# PedalBoard.net
KiCad netlist of a schematic drawn in Altium Designer
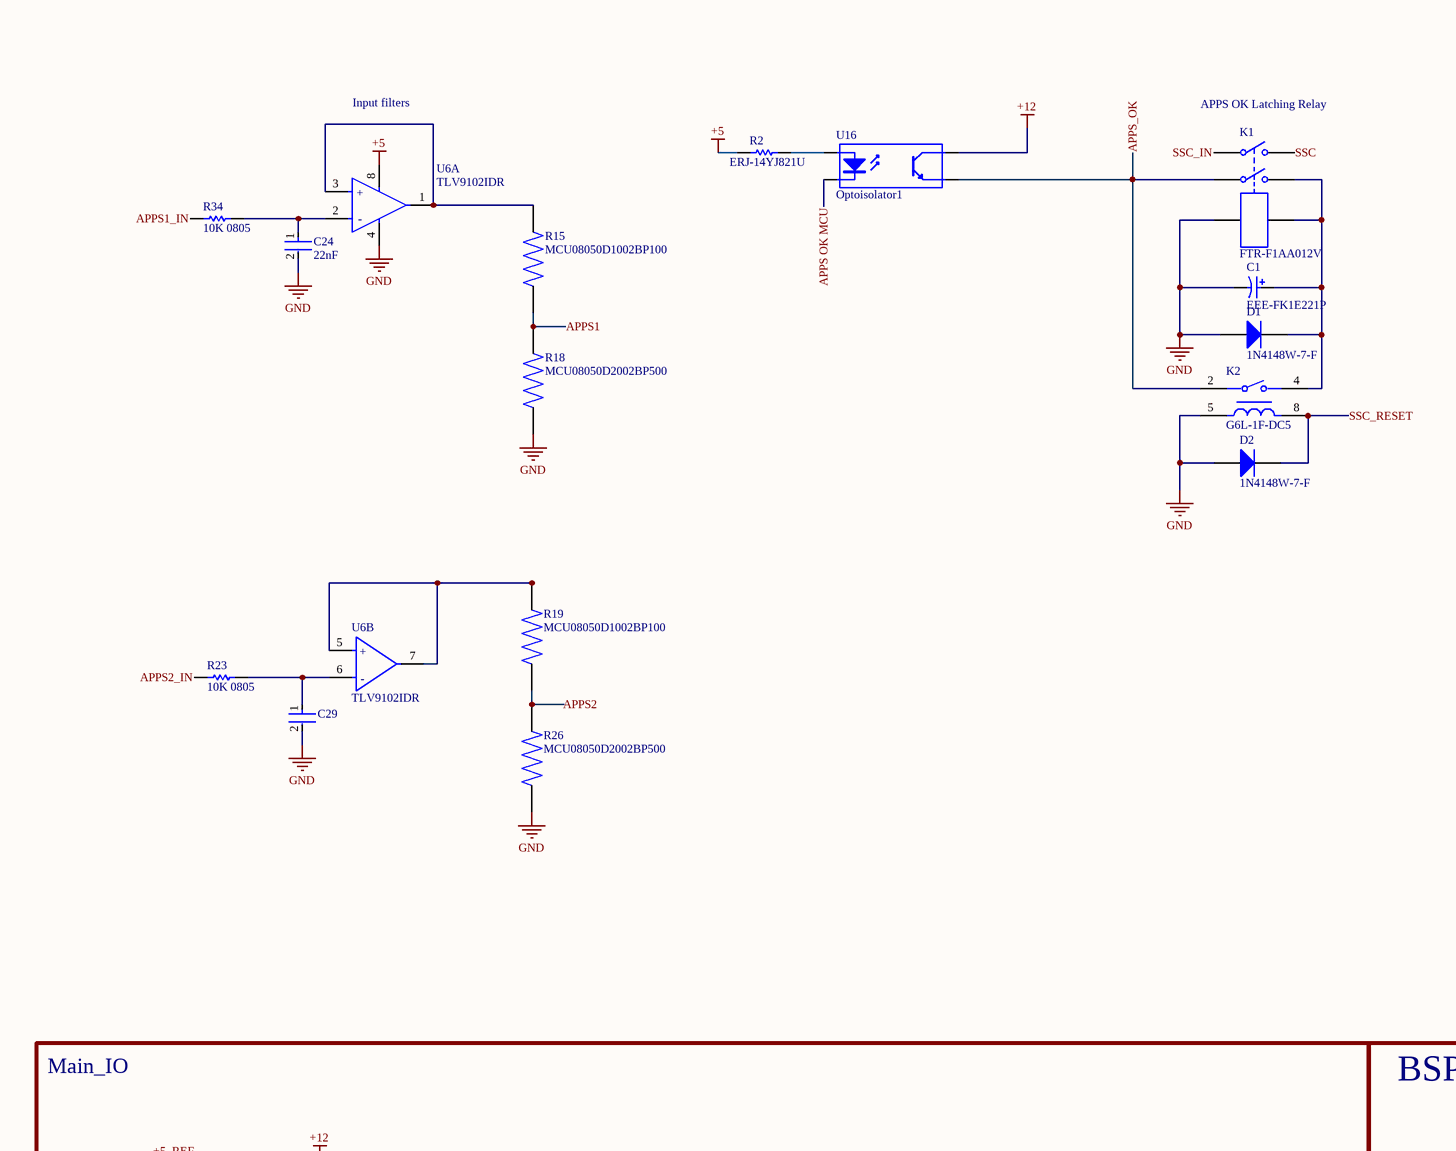
[diagram p0: PedalBoard.SchDoc, top left]
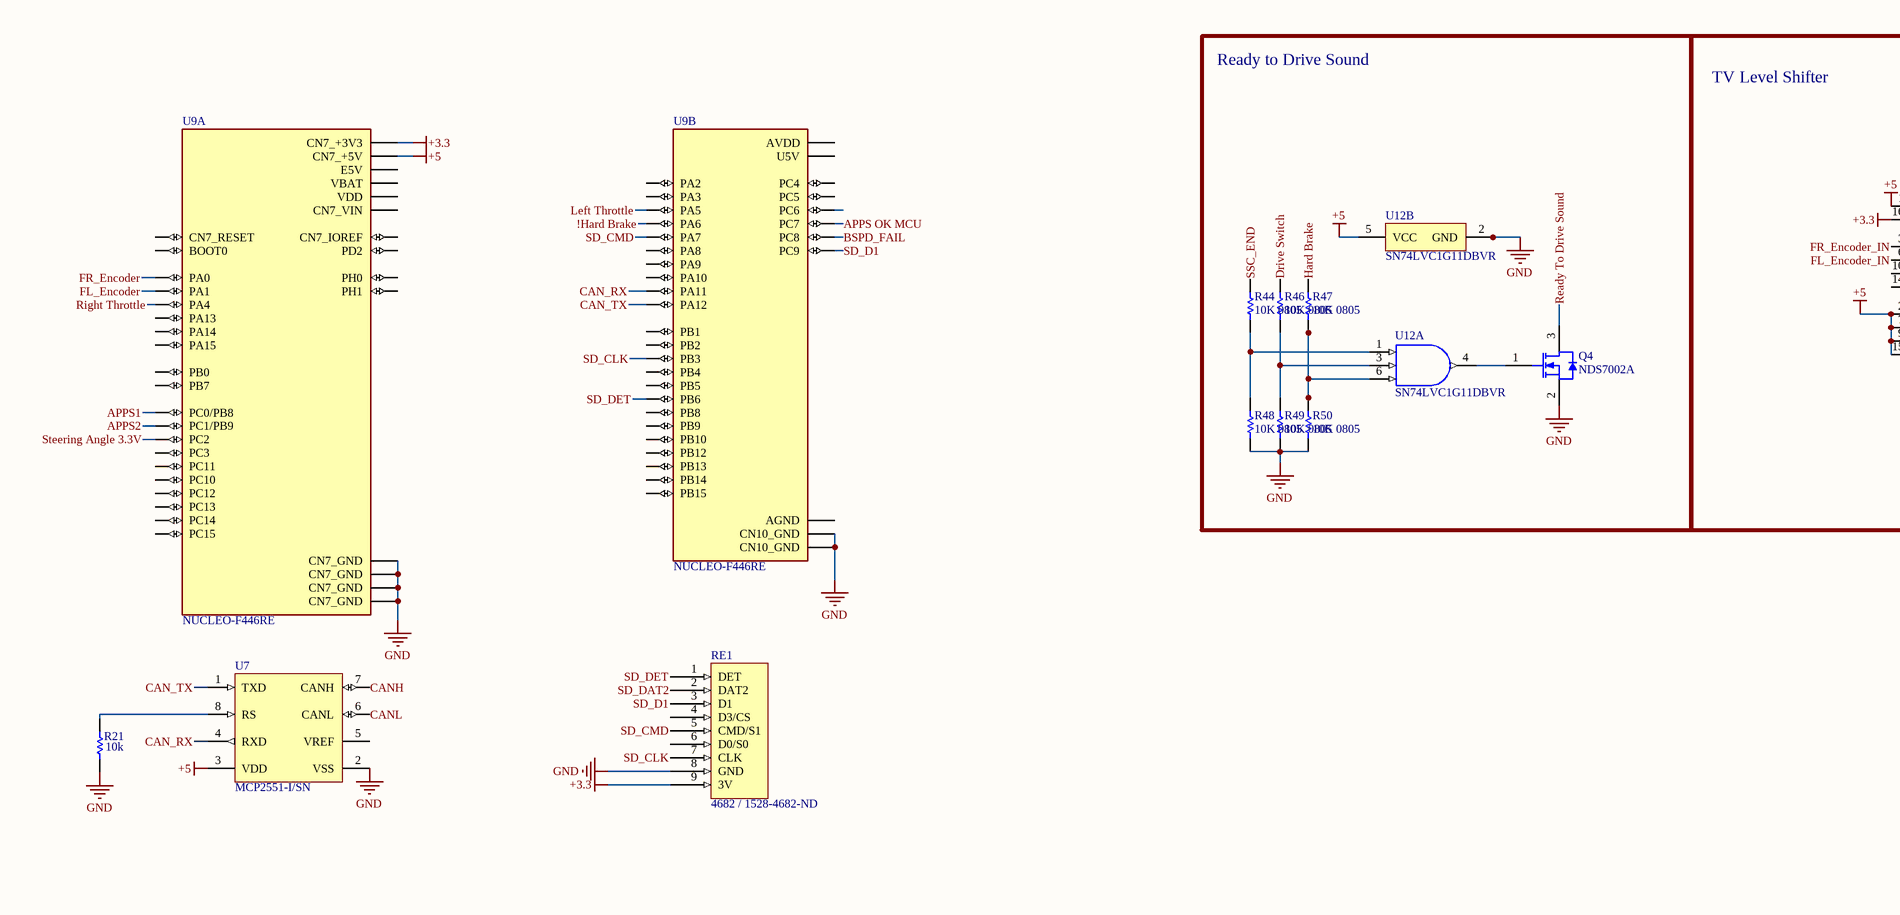
[diagram p1: PedalBoard.SchDoc, top middle]
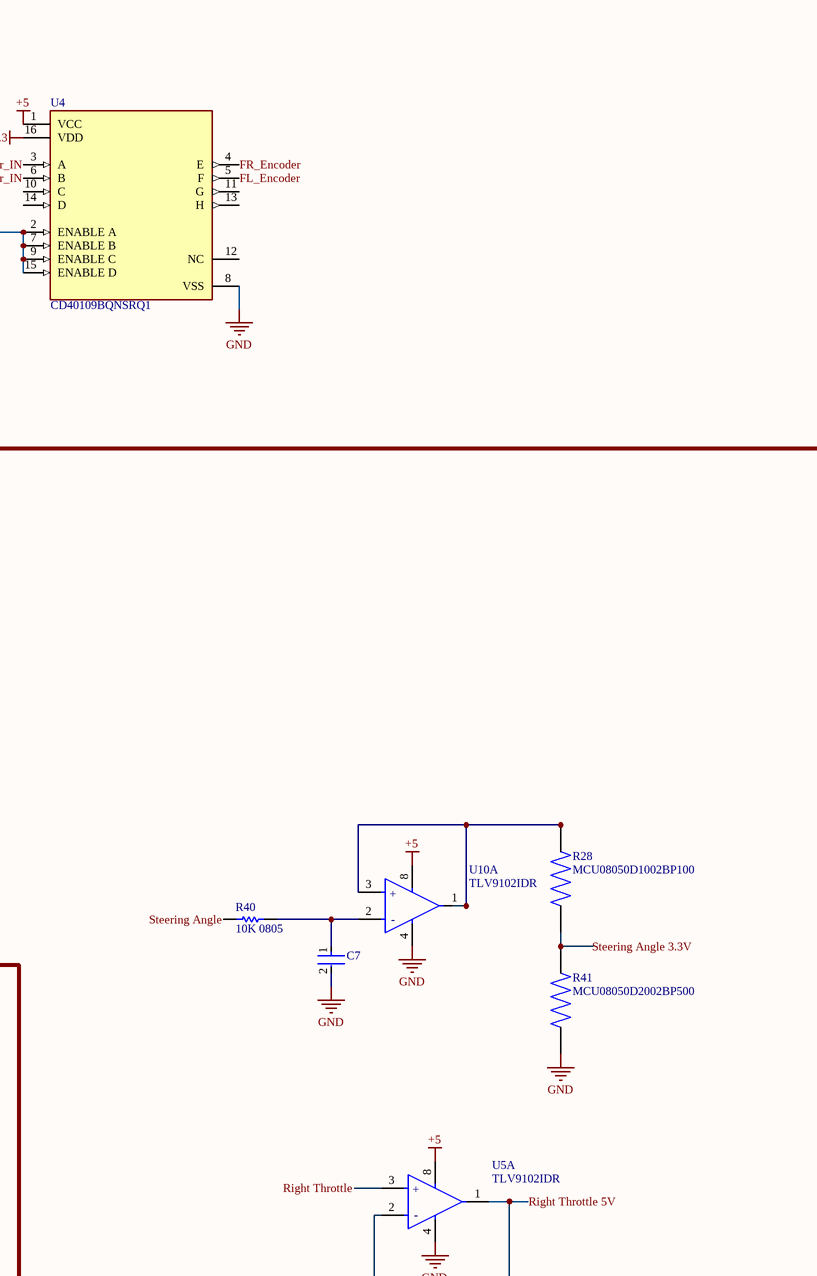
[diagram p2: PedalBoard.SchDoc, top right]
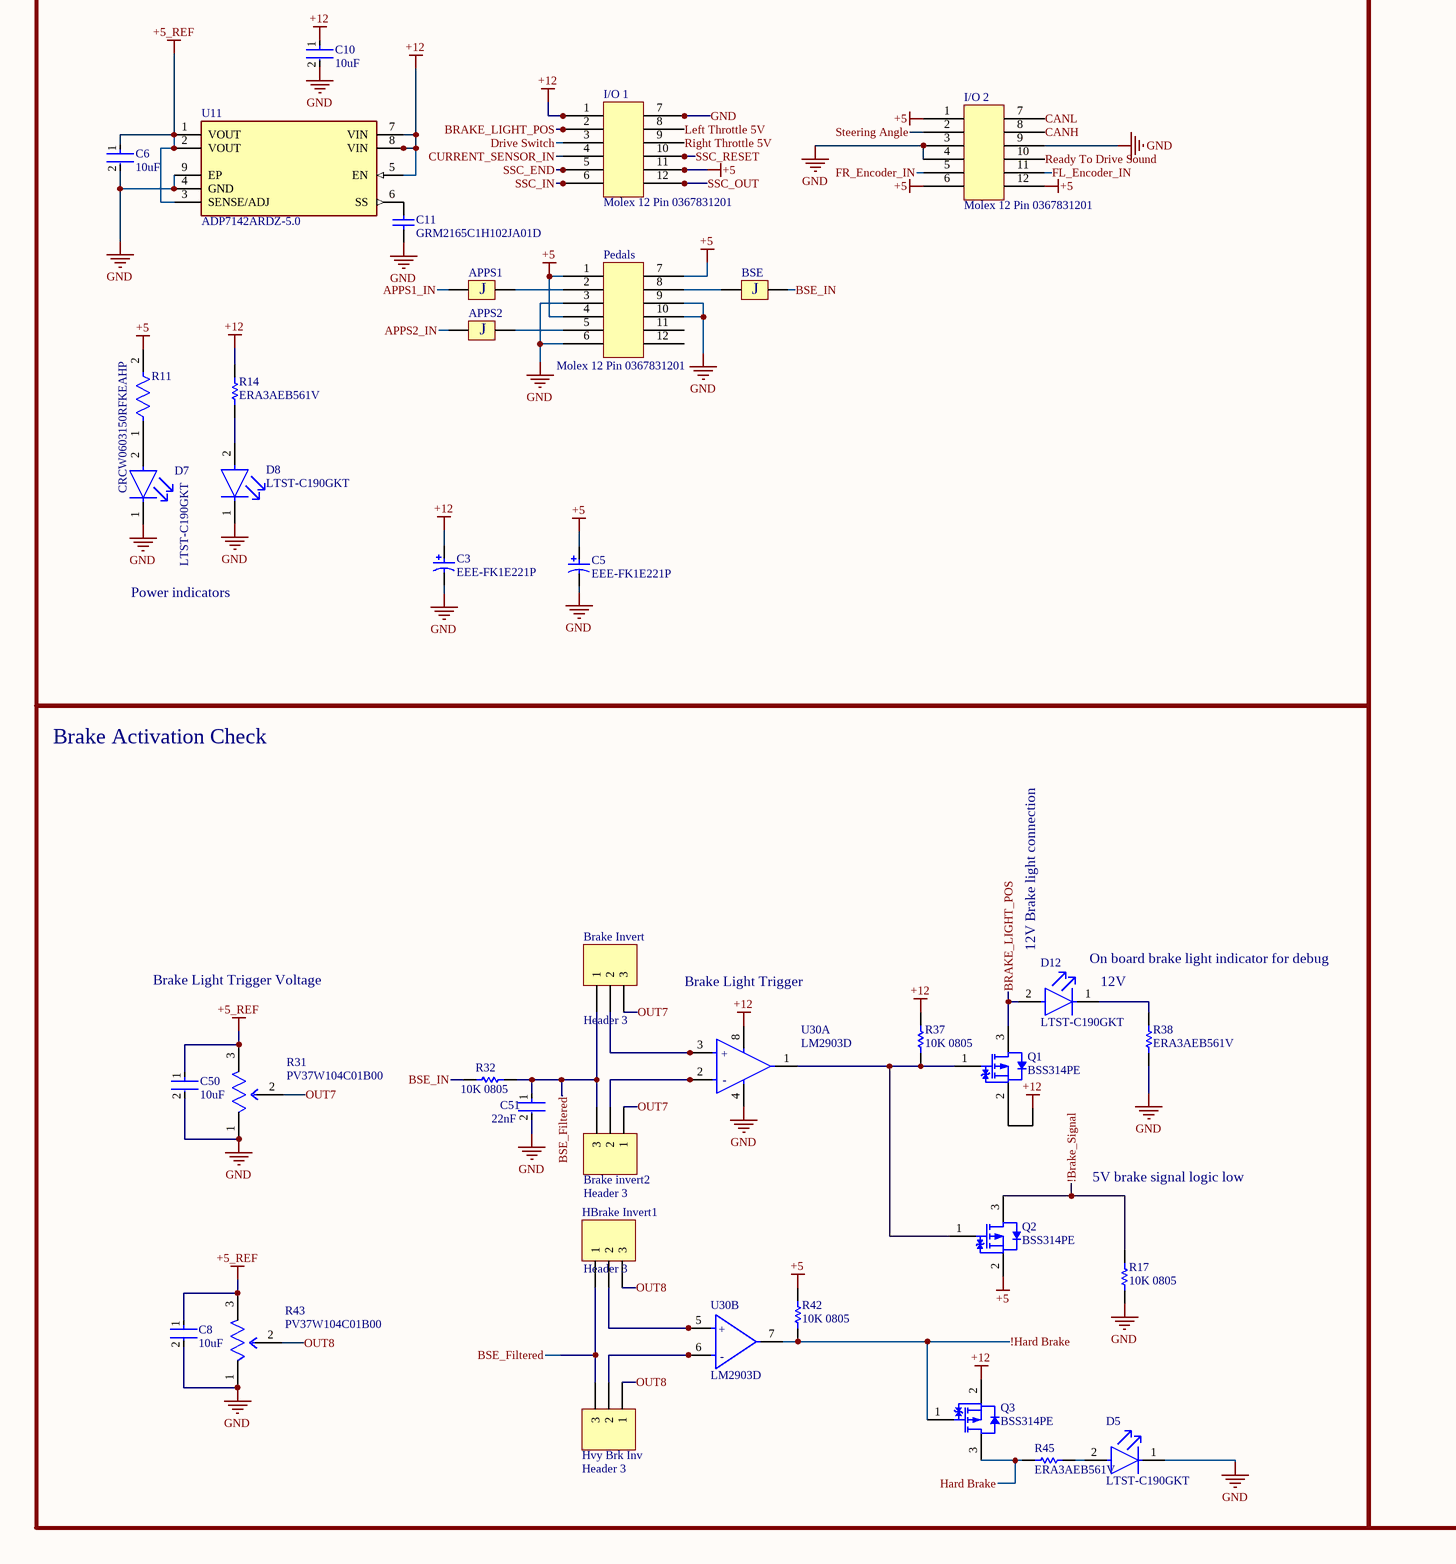
[diagram p3: PedalBoard.SchDoc, bottom left]
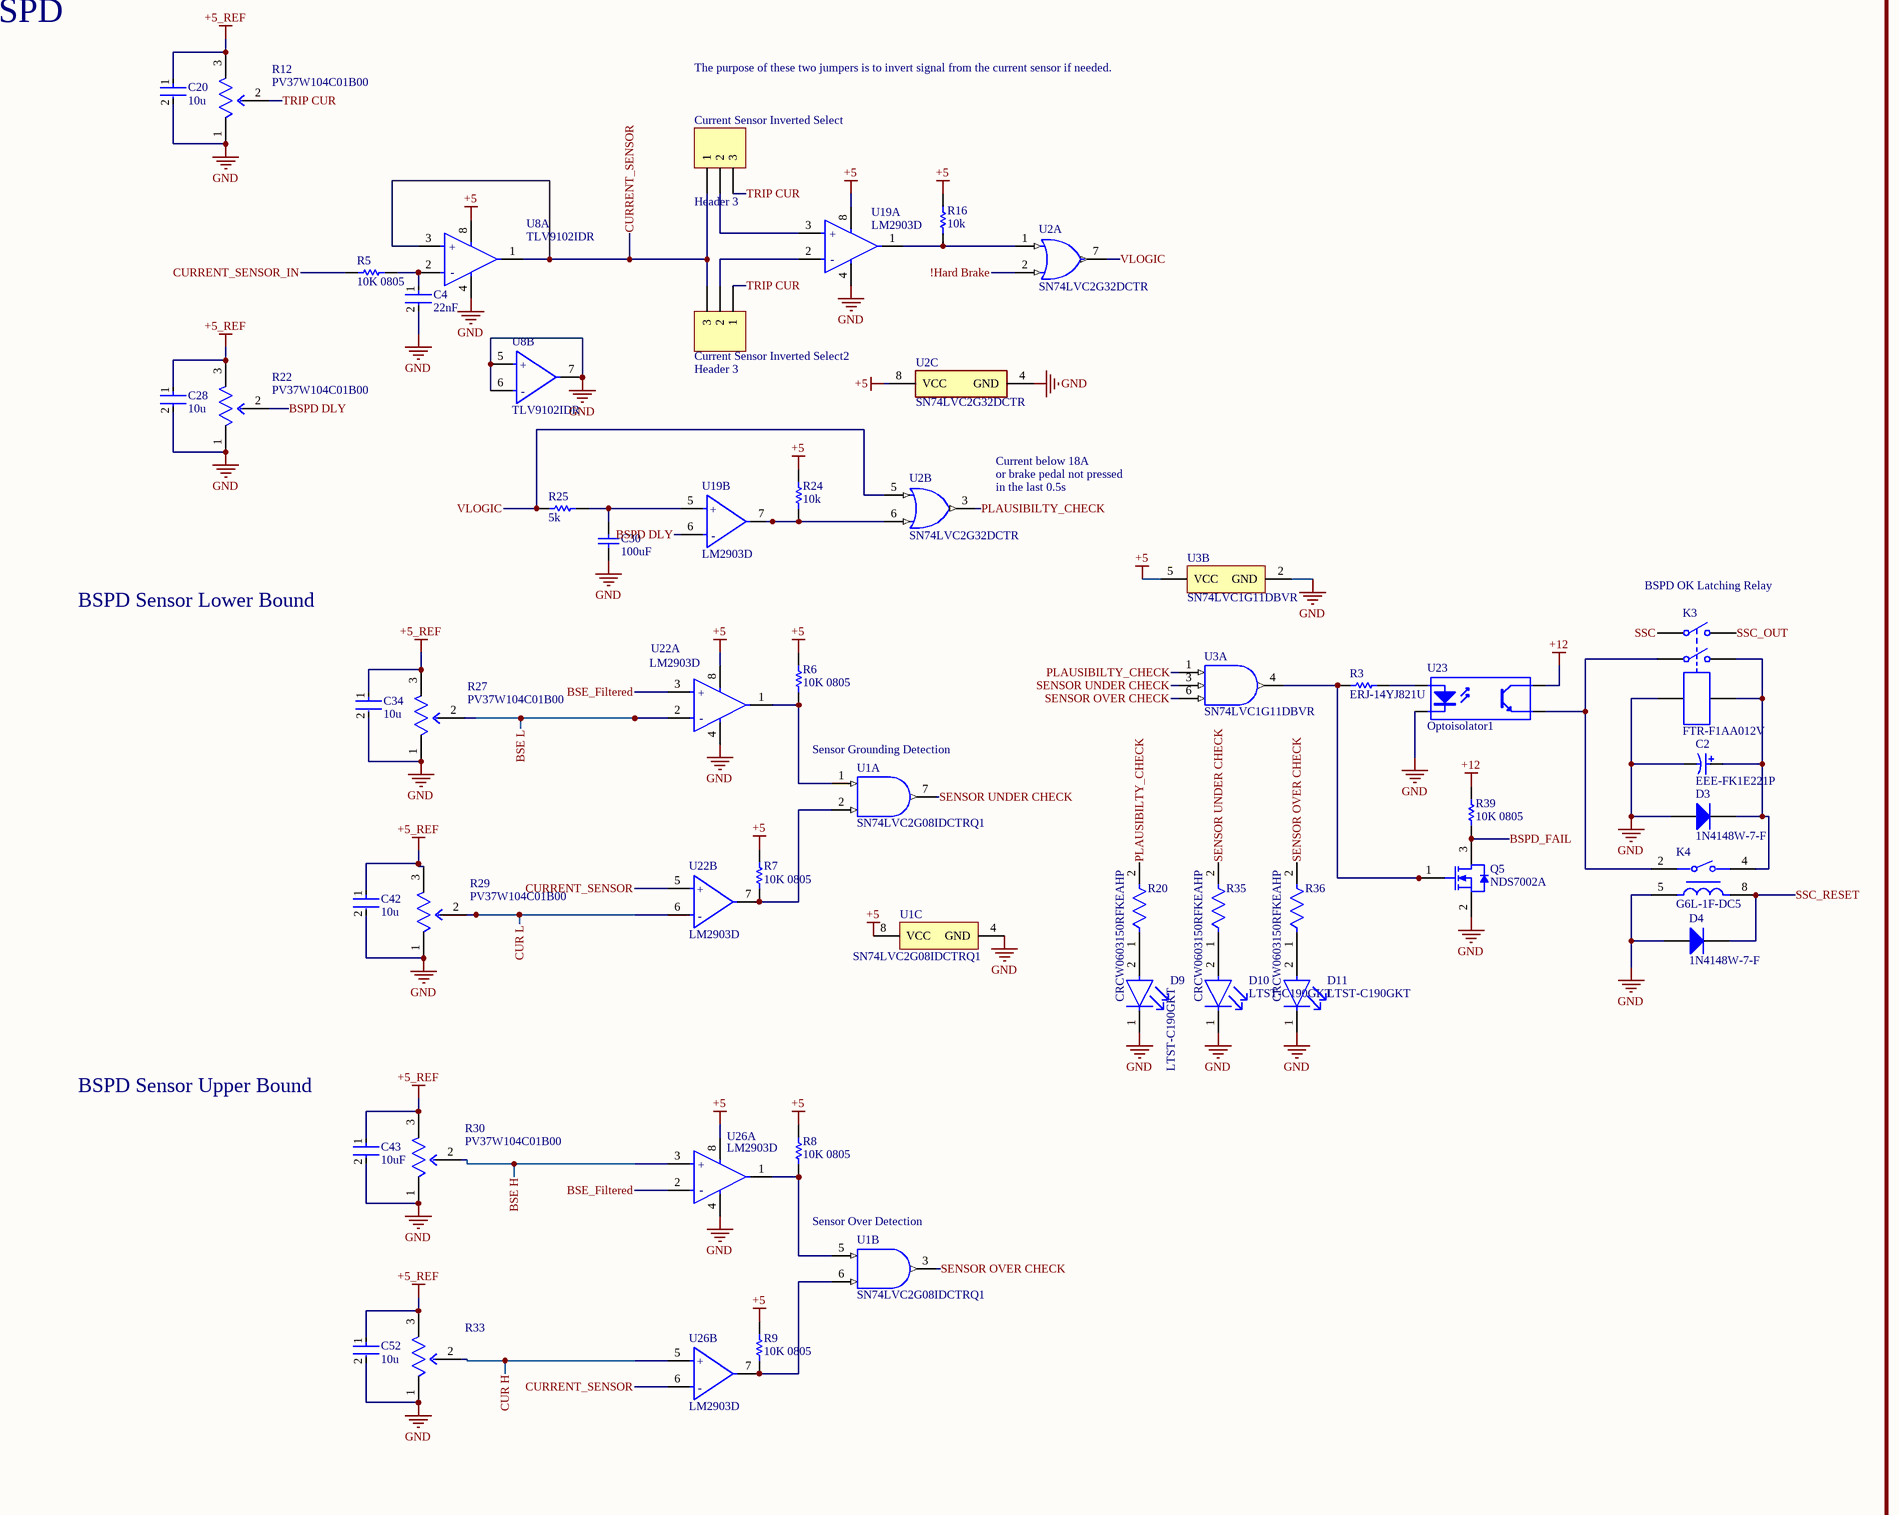
[diagram p4: PedalBoard.SchDoc, bottom middle]
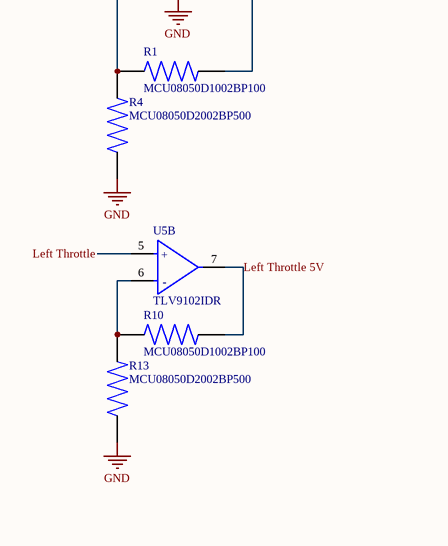
[diagram p5: PedalBoard.SchDoc, bottom right]

(export (version "E")
  (design (tool "Eeschema 10.0.6"))
  (components
    (comp (ref "APPS1")
      (value "Jumper Connector")
      (footprint "Jumper Connector")
      (libsource (lib "PedalControl") (part "Jumper Connector"))
    )
    (comp (ref "APPS2")
      (value "Jumper Connector")
      (footprint "Jumper Connector")
      (libsource (lib "PedalControl") (part "Jumper Connector"))
    )
    (comp (ref "Brake Invert")
      (value "Header 3")
      (footprint "HDR1X3")
      (description "Header, 3-Pin")
      (fields (field (name "PUBLISHER") "Altium Limited"))
      (libsource (lib "Miscellaneous Connectors") (part "Header 3"))
    )
    (comp (ref "Brake invert2")
      (value "Header 3")
      (footprint "HDR1X3")
      (description "Header, 3-Pin")
      (fields (field (name "PUBLISHER") "Altium Limited"))
      (libsource (lib "") (part "Header 3_1"))
    )
    (comp (ref "BSE")
      (value "Jumper Connector")
      (footprint "Jumper Connector")
      (libsource (lib "PedalControl") (part "Jumper Connector"))
    )
    (comp (ref "C1")
      (value "EEE-FK1E221P")
      (footprint "PNSC-EEE-FK1E221P_N")
      (fields (field (name "MANUFACTURER") "Panasonic"))
      (libsource (lib "Altium Content Vault") (part "CAP-P-2"))
    )
    (comp (ref "C2")
      (value "EEE-FK1E221P")
      (footprint "PNSC-EEE-FK1E221P_N")
      (fields (field (name "MANUFACTURER") "Panasonic"))
      (libsource (lib "Altium Content Vault") (part "CAP-P-2"))
    )
    (comp (ref "C3")
      (value "EEE-FK1E221P")
      (footprint "PNSC-EEE-FK1E221P_N")
      (fields (field (name "MANUFACTURER") "Panasonic"))
      (libsource (lib "Altium Content Vault") (part "CAP-P-2"))
    )
    (comp (ref "C4")
      (value "22nF")
      (footprint "FP-C0805C-DN-MFG")
      (description "CAP CER 0.022UF 50V X7R 0805")
      (fields
        (field (name "MANUFACTURER") "KEMET")
        (field (name "MANUFACTURER PART NUMBER") "C0805C223K5RACTU")
      )
      (libsource (lib "Altium Content Vault") (part "b4654b650e69147ec39a6b967a45e02"))
    )
    (comp (ref "C5")
      (value "EEE-FK1E221P")
      (footprint "PNSC-EEE-FK1E221P_N")
      (fields (field (name "MANUFACTURER") "Panasonic"))
      (libsource (lib "Altium Content Vault") (part "CAP-P-2"))
    )
    (comp (ref "C6")
      (value "10uF")
      (footprint "FP-C0603C106M9PACTU-MFG")
      (description "CAP CER 10UF 6.3V X5R 0603")
      (fields
        (field (name "MANUFACTURER PART NUMBER") "C0603C106M9PACTU")
        (field (name "MANUFACTURER") "Kemet")
      )
      (libsource (lib "Altium Content Vault") (part "b4654b650e69147ec39a6b967a45e02"))
    )
    (comp (ref "C7")
      (value "C0805C223K5RACTU")
      (footprint "FP-C0805C-DN-MFG")
      (description "CAP CER 0.022UF 50V X7R 0805")
      (fields
        (field (name "MANUFACTURER") "KEMET")
        (field (name "OCTOPART") "https://octopart.com/c0805c223k5ractu-kemet-145968")
      )
      (libsource (lib "Altium Content Vault") (part "b4654b650e69147ec39a6b967a45e02"))
    )
    (comp (ref "C8")
      (value "10uF")
      (footprint "FP-C0603C106M9PACTU-MFG")
      (description "CAP CER 10UF 6.3V X5R 0603")
      (fields
        (field (name "MANUFACTURER PART NUMBER") "C0603C106M9PACTU")
        (field (name "MANUFACTURER") "Kemet")
      )
      (libsource (lib "Altium Content Vault") (part "b4654b650e69147ec39a6b967a45e02"))
    )
    (comp (ref "C10")
      (value "10uF")
      (footprint "FP-C0603C106M9PACTU-MFG")
      (description "CAP CER 10UF 6.3V X5R 0603")
      (fields
        (field (name "MANUFACTURER PART NUMBER") "C0603C106M9PACTU")
        (field (name "MANUFACTURER") "Kemet")
      )
      (libsource (lib "Altium Content Vault") (part "b4654b650e69147ec39a6b967a45e02"))
    )
    (comp (ref "C11")
      (value "GRM2165C1H102JA01D")
      (footprint "CAPC2013X70X45NL10T25")
      (fields (field (name "MANUFACTURER") "Murata"))
      (libsource (lib "Altium Content Vault") (part "CAP"))
    )
    (comp (ref "C20")
      (value "10u")
      (footprint "FP-C0603C106M9PACTU-MFG")
      (description "CAP CER 10UF 6.3V X5R 0603")
      (fields
        (field (name "MANUFACTURER PART NUMBER") "C0603C106M9PACTU")
        (field (name "MANUFACTURER") "Kemet")
      )
      (libsource (lib "Altium Content Vault") (part "b4654b650e69147ec39a6b967a45e02"))
    )
    (comp (ref "C24")
      (value "22nF")
      (footprint "FP-C0805C-DN-MFG")
      (description "CAP CER 0.022UF 50V X7R 0805")
      (fields
        (field (name "MANUFACTURER") "KEMET")
        (field (name "MANUFACTURER PART NUMBER") "C0805C223K5RACTU")
      )
      (libsource (lib "Altium Content Vault") (part "b4654b650e69147ec39a6b967a45e02"))
    )
    (comp (ref "C28")
      (value "10u")
      (footprint "FP-C0603C106M9PACTU-MFG")
      (description "CAP CER 10UF 6.3V X5R 0603")
      (fields
        (field (name "MANUFACTURER PART NUMBER") "C0603C106M9PACTU")
        (field (name "MANUFACTURER") "Kemet")
      )
      (libsource (lib "Altium Content Vault") (part "b4654b650e69147ec39a6b967a45e02"))
    )
    (comp (ref "C29")
      (value "C0805C223K5RACTU")
      (footprint "FP-C0805C-DN-MFG")
      (description "CAP CER 0.022UF 50V X7R 0805")
      (fields
        (field (name "MANUFACTURER") "KEMET")
        (field (name "OCTOPART") "https://octopart.com/c0805c223k5ractu-kemet-145968")
      )
      (libsource (lib "Altium Content Vault") (part "b4654b650e69147ec39a6b967a45e02"))
    )
    (comp (ref "C30")
      (value "100uF")
      (footprint "CAPC1608X90X35LL15T15")
      (fields (field (name "MANUFACTURER") "Kemet") (field (name "PART NUMBER") "C0603C105K3PAC7867"))
      (libsource (lib "Altium Content Vault") (part "CAP"))
    )
    (comp (ref "C34")
      (value "10u")
      (footprint "FP-C0603C106M9PACTU-MFG")
      (description "CAP CER 10UF 6.3V X5R 0603")
      (fields
        (field (name "MANUFACTURER PART NUMBER") "C0603C106M9PACTU")
        (field (name "MANUFACTURER") "Kemet")
      )
      (libsource (lib "Altium Content Vault") (part "b4654b650e69147ec39a6b967a45e02"))
    )
    (comp (ref "C42")
      (value "10u")
      (footprint "FP-C0603C106M9PACTU-MFG")
      (description "CAP CER 10UF 6.3V X5R 0603")
      (fields
        (field (name "MANUFACTURER PART NUMBER") "C0603C106M9PACTU")
        (field (name "MANUFACTURER") "Kemet")
      )
      (libsource (lib "Altium Content Vault") (part "b4654b650e69147ec39a6b967a45e02"))
    )
    (comp (ref "C43")
      (value "10uF")
      (footprint "FP-C0603C106M9PACTU-MFG")
      (description "CAP CER 10UF 6.3V X5R 0603")
      (fields
        (field (name "MANUFACTURER PART NUMBER") "C0603C106M9PACTU")
        (field (name "MANUFACTURER") "Kemet")
      )
      (libsource (lib "Altium Content Vault") (part "b4654b650e69147ec39a6b967a45e02"))
    )
    (comp (ref "C50")
      (value "10uF")
      (footprint "FP-C0603C106M9PACTU-MFG")
      (description "CAP CER 10UF 6.3V X5R 0603")
      (fields
        (field (name "MANUFACTURER PART NUMBER") "C0603C106M9PACTU")
        (field (name "MANUFACTURER") "Kemet")
      )
      (libsource (lib "Altium Content Vault") (part "b4654b650e69147ec39a6b967a45e02"))
    )
    (comp (ref "C51")
      (value "22nF")
      (footprint "FP-C0805C-DN-MFG")
      (description "CAP CER 0.022UF 50V X7R 0805")
      (fields
        (field (name "MANUFACTURER") "KEMET")
        (field (name "MANUFACTURER PART NUMBER") "C0805C223K5RACTU")
      )
      (libsource (lib "Altium Content Vault") (part "b4654b650e69147ec39a6b967a45e02"))
    )
    (comp (ref "C52")
      (value "10u")
      (footprint "FP-C0603C106M9PACTU-MFG")
      (description "CAP CER 10UF 6.3V X5R 0603")
      (fields
        (field (name "MANUFACTURER PART NUMBER") "C0603C106M9PACTU")
        (field (name "MANUFACTURER") "Kemet")
      )
      (libsource (lib "Altium Content Vault") (part "b4654b650e69147ec39a6b967a45e02"))
    )
    (comp (ref "Current Sensor Inverted Select")
      (value "Header 3")
      (footprint "HDR1X3")
      (description "Header, 3-Pin")
      (fields (field (name "PUBLISHER") "Altium Limited"))
      (libsource (lib "Miscellaneous Connectors") (part "Header 3"))
    )
    (comp (ref "Current Sensor Inverted Select2")
      (value "Header 3")
      (footprint "HDR1X3")
      (description "Header, 3-Pin")
      (fields (field (name "PUBLISHER") "Altium Limited"))
      (libsource (lib "") (part "Header 3_1"))
    )
    (comp (ref "D1")
      (value "1N4148W-7-F")
      (footprint "DIOD-SOD123-2_V")
      (description "Fast Switching Diode, 100 V, 0.15 A, -65 to 150 degC, 2-Pin?SOD123, RoHS, Tape and Reel")
      (fields (field (name "MANUFACTURER") "DiodesIncorporated"))
      (libsource (lib "Altium Content Vault") (part "D-AK-2"))
    )
    (comp (ref "D2")
      (value "1N4148W-7-F")
      (footprint "DIOD-SOD123-2_V")
      (description "Fast Switching Diode, 100 V, 0.15 A, -65 to 150 degC, 2-Pin?SOD123, RoHS, Tape and Reel")
      (fields (field (name "MANUFACTURER") "DiodesIncorporated"))
      (libsource (lib "Altium Content Vault") (part "D-AK-2"))
    )
    (comp (ref "D3")
      (value "1N4148W-7-F")
      (footprint "DIOD-SOD123-2_V")
      (description "Fast Switching Diode, 100 V, 0.15 A, -65 to 150 degC, 2-Pin?SOD123, RoHS, Tape and Reel")
      (fields (field (name "MANUFACTURER") "DiodesIncorporated"))
      (libsource (lib "Altium Content Vault") (part "D-AK-2"))
    )
    (comp (ref "D4")
      (value "1N4148W-7-F")
      (footprint "DIOD-SOD123-2_V")
      (description "Fast Switching Diode, 100 V, 0.15 A, -65 to 150 degC, 2-Pin?SOD123, RoHS, Tape and Reel")
      (fields (field (name "MANUFACTURER") "DiodesIncorporated"))
      (libsource (lib "Altium Content Vault") (part "D-AK-2"))
    )
    (comp (ref "D5")
      (value "LTST-C190GKT")
      (footprint "FP-LTST-C190GKT-MFG")
      (description "LED GREEN CLEAR CHIP SMD")
      (fields (field (name "VOLTAGE") "2V"))
      (libsource (lib "Altium Content Vault") (part "8706943c75ba83719d021d2fdc84c58"))
    )
    (comp (ref "D7")
      (value "LTST-C190GKT")
      (footprint "FP-LTST-C190GKT-MFG")
      (description "LED GREEN CLEAR CHIP SMD")
      (fields (field (name "VOLTAGE") "2V"))
      (libsource (lib "Altium Content Vault") (part "8706943c75ba83719d021d2fdc84c58"))
    )
    (comp (ref "D8")
      (value "LTST-C190GKT")
      (footprint "FP-LTST-C190GKT-MFG")
      (description "LED GREEN CLEAR CHIP SMD")
      (fields (field (name "VOLTAGE") "2V"))
      (libsource (lib "Altium Content Vault") (part "8706943c75ba83719d021d2fdc84c58"))
    )
    (comp (ref "D9")
      (value "LTST-C190GKT")
      (footprint "FP-LTST-C190GKT-MFG")
      (description "LED GREEN CLEAR CHIP SMD")
      (fields (field (name "VOLTAGE") "2V"))
      (libsource (lib "Altium Content Vault") (part "8706943c75ba83719d021d2fdc84c58"))
    )
    (comp (ref "D10")
      (value "LTST-C190GKT")
      (footprint "FP-LTST-C190GKT-MFG")
      (description "LED GREEN CLEAR CHIP SMD")
      (fields (field (name "VOLTAGE") "2V"))
      (libsource (lib "Altium Content Vault") (part "8706943c75ba83719d021d2fdc84c58"))
    )
    (comp (ref "D11")
      (value "LTST-C190GKT")
      (footprint "FP-LTST-C190GKT-MFG")
      (description "LED GREEN CLEAR CHIP SMD")
      (fields (field (name "VOLTAGE") "2V"))
      (libsource (lib "Altium Content Vault") (part "8706943c75ba83719d021d2fdc84c58"))
    )
    (comp (ref "D12")
      (value "LTST-C190GKT")
      (footprint "FP-LTST-C190GKT-MFG")
      (description "LED GREEN CLEAR CHIP SMD")
      (fields (field (name "VOLTAGE") "2V"))
      (libsource (lib "Altium Content Vault") (part "8706943c75ba83719d021d2fdc84c58"))
    )
    (comp (ref "HBrake Invert1")
      (value "Header 3")
      (footprint "HDR1X3")
      (description "Header, 3-Pin")
      (fields (field (name "PUBLISHER") "Altium Limited"))
      (libsource (lib "Miscellaneous Connectors") (part "Header 3"))
    )
    (comp (ref "Hvy Brk Inv")
      (value "Header 3")
      (footprint "HDR1X3")
      (description "Header, 3-Pin")
      (fields (field (name "PUBLISHER") "Altium Limited"))
      (libsource (lib "") (part "Header 3_1"))
    )
    (comp (ref "I/O 1")
      (value "Molex 12 Pin 0367831201")
      (footprint "Molex 12 pos 0367831201 - duplicate")
      (libsource (lib "PedalControl") (part "Molex 12 Pin 0367831201"))
    )
    (comp (ref "I/O 2")
      (value "Molex 12 Pin 0367831201")
      (footprint "Molex 12 pos 0367831201 - duplicate")
      (libsource (lib "PedalControl") (part "Molex 12 Pin 0367831201"))
    )
    (comp (ref "K1")
      (value "FTR-F1AA012V")
      (footprint "FTR-F1AA012V")
      (description "Dual-Pole Single-Throw Relay")
      (fields (field (name "PUBLISHER") "Altium Limited"))
      (libsource (lib "Miscellaneous Devices") (part "Relay-DPST"))
    )
    (comp (ref "K2")
      (value "G6L-1F-DC5")
      (footprint "FP-G6L-1F-DC5-MFG")
      (description "RELAY TELECOM SPST 1A 5VDC")
      (fields
        (field (name "MANUFACTURER") "Omron")
        (field (name "OCTOPART") "https://octopart.com/g6l-1f+dc5-omron-18903080")
      )
      (libsource (lib "Altium Content Vault") (part "0b4cad2df39780911da7817dc4dbd4a"))
    )
    (comp (ref "K3")
      (value "FTR-F1AA012V")
      (footprint "FTR-F1AA012V")
      (description "Dual-Pole Single-Throw Relay")
      (fields (field (name "PUBLISHER") "Altium Limited"))
      (libsource (lib "Miscellaneous Devices") (part "Relay-DPST"))
    )
    (comp (ref "K4")
      (value "G6L-1F-DC5")
      (footprint "FP-G6L-1F-DC5-MFG")
      (description "RELAY TELECOM SPST 1A 5VDC")
      (fields
        (field (name "MANUFACTURER") "Omron")
        (field (name "OCTOPART") "https://octopart.com/g6l-1f+dc5-omron-18903080")
      )
      (libsource (lib "Altium Content Vault") (part "0b4cad2df39780911da7817dc4dbd4a"))
    )
    (comp (ref "Pedals")
      (value "Molex 12 Pin 0367831201")
      (footprint "Molex 12 pos 0367831201 - duplicate")
      (libsource (lib "PedalControl") (part "Molex 12 Pin 0367831201"))
    )
    (comp (ref "Q1")
      (value "BSS314PE")
      (footprint "INF-PG-SOT23_N")
      (fields (field (name "MANUFACTURER") "Infineon"))
      (libsource (lib "Altium Content Vault") (part "INF-BSS3XXPE-PG-SOT23-3"))
    )
    (comp (ref "Q2")
      (value "BSS314PE")
      (footprint "INF-PG-SOT23_N")
      (fields (field (name "MANUFACTURER") "Infineon"))
      (libsource (lib "Altium Content Vault") (part "INF-BSS3XXPE-PG-SOT23-3"))
    )
    (comp (ref "Q3")
      (value "BSS314PE")
      (footprint "INF-PG-SOT23_N")
      (fields (field (name "MANUFACTURER") "Infineon"))
      (libsource (lib "Altium Content Vault") (part "INF-BSS3XXPE-PG-SOT23-3"))
    )
    (comp (ref "Q4")
      (value "NDS7002A")
      (footprint "FAIR-SOT23-3_V")
      (fields (field (name "MANUFACTURER") "Fairchild Semiconductor"))
      (libsource (lib "Altium Content Vault") (part "NEMOS-GSD-3"))
    )
    (comp (ref "Q5")
      (value "NDS7002A")
      (footprint "FAIR-SOT23-3_V")
      (fields (field (name "MANUFACTURER") "Fairchild Semiconductor"))
      (libsource (lib "Altium Content Vault") (part "NEMOS-GSD-3"))
    )
    (comp (ref "R1")
      (value "MCU08050D1002BP100")
      (footprint "MCU08050D1002BP100:RESC2012X55N")
      (description "Res Thin Film 0805 10K Ohm 0.1% 0.125W(1/8W) Â±25ppm/C SMD Automotive Medical T/R")
      (fields (field (name "MF") "{'manufacturer': u'Vishay'}"))
      (libsource (lib "*") (part "MCU08050D1002BP100"))
    )
    (comp (ref "R2")
      (value "ERJ-14YJ821U")
      (footprint "RESC3225X70X50LL20T20")
      (description "820")
      (fields (field (name "MANUFACTURER") "Panasonic"))
      (libsource (lib "Altium Content Vault") (part "RES"))
    )
    (comp (ref "R3")
      (value "ERJ-14YJ821U")
      (footprint "RESC3225X70X50LL20T20")
      (description "820")
      (fields (field (name "MANUFACTURER") "Panasonic"))
      (libsource (lib "Altium Content Vault") (part "RES"))
    )
    (comp (ref "R4")
      (value "MCU08050D2002BP500")
      (footprint "MCU08050D2002BP500:RESC2012X55N")
      (description "RES -FILM RESISTORS-THICK FILM CHIP")
      (fields (field (name "MF") "{'manufacturer': u'Vishay'}"))
      (libsource (lib "*") (part "MCU08050D2002BP500"))
    )
    (comp (ref "R5")
      (value "10K 0805")
      (footprint "RESC2013X60X35NL10T20")
      (description "Chip Resistor, 10 KOhm, +/- 1%, 0.125 W, -55 to 155 degC, 0805 (2012 Metric), RoHS, Tape and Reel")
      (fields (field (name "MANUFACTURER") "Yageo"))
      (libsource (lib "Altium Content Vault") (part "RES-2"))
    )
    (comp (ref "R6")
      (value "10K 0805")
      (footprint "RESC2013X60X35NL10T20")
      (description "Chip Resistor, 10 KOhm, +/- 1%, 0.125 W, -55 to 155 degC, 0805 (2012 Metric), RoHS, Tape and Reel")
      (fields (field (name "MANUFACTURER") "Yageo"))
      (libsource (lib "Altium Content Vault") (part "RES-2"))
    )
    (comp (ref "R7")
      (value "10K 0805")
      (footprint "RESC2013X60X35NL10T20")
      (description "Chip Resistor, 10 KOhm, +/- 1%, 0.125 W, -55 to 155 degC, 0805 (2012 Metric), RoHS, Tape and Reel")
      (fields (field (name "MANUFACTURER") "Yageo"))
      (libsource (lib "Altium Content Vault") (part "RES-2"))
    )
    (comp (ref "R8")
      (value "10K 0805")
      (footprint "RESC2013X60X35NL10T20")
      (description "Chip Resistor, 10 KOhm, +/- 1%, 0.125 W, -55 to 155 degC, 0805 (2012 Metric), RoHS, Tape and Reel")
      (fields (field (name "MANUFACTURER") "Yageo"))
      (libsource (lib "Altium Content Vault") (part "RES-2"))
    )
    (comp (ref "R9")
      (value "10K 0805")
      (footprint "RESC2013X60X35NL10T20")
      (description "Chip Resistor, 10 KOhm, +/- 1%, 0.125 W, -55 to 155 degC, 0805 (2012 Metric), RoHS, Tape and Reel")
      (fields (field (name "MANUFACTURER") "Yageo"))
      (libsource (lib "Altium Content Vault") (part "RES-2"))
    )
    (comp (ref "R10")
      (value "MCU08050D1002BP100")
      (footprint "MCU08050D1002BP100:RESC2012X55N")
      (description "Res Thin Film 0805 10K Ohm 0.1% 0.125W(1/8W) Â±25ppm/C SMD Automotive Medical T/R")
      (fields (field (name "MF") "{'manufacturer': u'Vishay'}"))
      (libsource (lib "*") (part "MCU08050D1002BP100"))
    )
    (comp (ref "R11")
      (value "CRCW0603150RFKEAHP")
      (footprint "FP-CRCW0603-HPe3-MFG")
      (description "RES Thick Film, 150Ω, 1%, 0.33W, 100ppm/°C, 0603")
      (fields (field (name "TOLERANCE") "1%"))
      (libsource (lib "Altium Content Vault") (part "1029c3af85768c4190bb7ad29bc67b5"))
    )
    (comp (ref "R12")
      (value "PV37W104C01B00")
      (footprint "FP-PV37W104C01B00-MFG")
      (description "12-Turn Through Hole Trimmer Resistor with Pin Terminations, 10% 1/4W 150ppm/C")
      (fields (field (name "TOLERANCE") "10%"))
      (libsource (lib "Altium Content Vault") (part "08526ac0d5a9b3c124616c1f8dc5852"))
    )
    (comp (ref "R13")
      (value "MCU08050D2002BP500")
      (footprint "MCU08050D2002BP500:RESC2012X55N")
      (description "RES -FILM RESISTORS-THICK FILM CHIP")
      (fields (field (name "MF") "{'manufacturer': u'Vishay'}"))
      (libsource (lib "*") (part "MCU08050D2002BP500"))
    )
    (comp (ref "R14")
      (value "ERA3AEB561V")
      (footprint "RESC1608X55X30LL20T20")
      (fields (field (name "MANUFACTURER") "Panasonic"))
      (libsource (lib "Altium Content Vault") (part "RES"))
    )
    (comp (ref "R15")
      (value "MCU08050D1002BP100")
      (footprint "MCU08050D1002BP100:RESC2012X55N")
      (description "Res Thin Film 0805 10K Ohm 0.1% 0.125W(1/8W) Â±25ppm/C SMD Automotive Medical T/R")
      (fields (field (name "MF") "{'manufacturer': u'Vishay'}"))
      (libsource (lib "*") (part "MCU08050D1002BP100"))
    )
    (comp (ref "R16")
      (value "10k")
      (footprint "RESC1609X55X30LL15T15")
      (description "Chip Resistor, 10 KOhm, +/- 1%, 0.1 W, -55 to 155 degC, 0603 (1608 Metric), RoHS, Tape and Reel")
      (fields (field (name "TOLERANCE") "1%") (field (name "MANUFACTURER") "Panasonic"))
      (libsource (lib "Altium Content Vault") (part "RES-2"))
    )
    (comp (ref "R17")
      (value "10K 0805")
      (footprint "RESC2013X60X35NL10T20")
      (description "Chip Resistor, 10 KOhm, +/- 1%, 0.125 W, -55 to 155 degC, 0805 (2012 Metric), RoHS, Tape and Reel")
      (fields (field (name "MANUFACTURER") "Yageo"))
      (libsource (lib "Altium Content Vault") (part "RES-2"))
    )
    (comp (ref "R18")
      (value "MCU08050D2002BP500")
      (footprint "MCU08050D2002BP500:RESC2012X55N")
      (description "RES -FILM RESISTORS-THICK FILM CHIP")
      (fields (field (name "MF") "{'manufacturer': u'Vishay'}"))
      (libsource (lib "*") (part "MCU08050D2002BP500"))
    )
    (comp (ref "R19")
      (value "MCU08050D1002BP100")
      (footprint "MCU08050D1002BP100:RESC2012X55N")
      (description "Res Thin Film 0805 10K Ohm 0.1% 0.125W(1/8W) Â±25ppm/C SMD Automotive Medical T/R")
      (fields (field (name "MF") "{'manufacturer': u'Vishay'}"))
      (libsource (lib "*") (part "MCU08050D1002BP100"))
    )
    (comp (ref "R20")
      (value "CRCW0603150RFKEAHP")
      (footprint "FP-CRCW0603-HPe3-MFG")
      (description "RES Thick Film, 150Ω, 1%, 0.33W, 100ppm/°C, 0603")
      (fields (field (name "TOLERANCE") "1%"))
      (libsource (lib "Altium Content Vault") (part "1029c3af85768c4190bb7ad29bc67b5"))
    )
    (comp (ref "R21")
      (value "10k")
      (footprint "RESC1609X55X30LL15T15")
      (description "Chip Resistor, 10 KOhm, +/- 1%, 0.1 W, -55 to 155 degC, 0603 (1608 Metric), RoHS, Tape and Reel")
      (fields (field (name "TOLERANCE") "1%") (field (name "MANUFACTURER") "Panasonic"))
      (libsource (lib "Altium Content Vault") (part "RES-2"))
    )
    (comp (ref "R22")
      (value "PV37W104C01B00")
      (footprint "FP-PV37W104C01B00-MFG")
      (description "12-Turn Through Hole Trimmer Resistor with Pin Terminations, 10% 1/4W 150ppm/C")
      (fields (field (name "TOLERANCE") "10%"))
      (libsource (lib "Altium Content Vault") (part "08526ac0d5a9b3c124616c1f8dc5852"))
    )
    (comp (ref "R23")
      (value "10K 0805")
      (footprint "RESC2013X60X35NL10T20")
      (description "Chip Resistor, 10 KOhm, +/- 1%, 0.125 W, -55 to 155 degC, 0805 (2012 Metric), RoHS, Tape and Reel")
      (fields (field (name "MANUFACTURER") "Yageo"))
      (libsource (lib "Altium Content Vault") (part "RES-2"))
    )
    (comp (ref "R24")
      (value "10k")
      (footprint "RESC1609X55X30LL15T15")
      (description "Chip Resistor, 10 KOhm, +/- 1%, 0.1 W, -55 to 155 degC, 0603 (1608 Metric), RoHS, Tape and Reel")
      (fields (field (name "TOLERANCE") "1%") (field (name "MANUFACTURER") "Panasonic"))
      (libsource (lib "Altium Content Vault") (part "RES-2"))
    )
    (comp (ref "R25")
      (value "5k")
      (footprint "RESC1609X55X30LL15T15")
      (description "Chip Resistor, 10 KOhm, +/- 1%, 0.1 W, -55 to 155 degC, 0603 (1608 Metric), RoHS, Tape and Reel")
      (fields (field (name "TOLERANCE") "1%") (field (name "MANUFACTURER") "Panasonic"))
      (libsource (lib "Altium Content Vault") (part "RES-2"))
    )
    (comp (ref "R26")
      (value "MCU08050D2002BP500")
      (footprint "MCU08050D2002BP500:RESC2012X55N")
      (description "RES -FILM RESISTORS-THICK FILM CHIP")
      (fields (field (name "MF") "{'manufacturer': u'Vishay'}"))
      (libsource (lib "*") (part "MCU08050D2002BP500"))
    )
    (comp (ref "R27")
      (value "PV37W104C01B00")
      (footprint "FP-PV37W104C01B00-MFG")
      (description "12-Turn Through Hole Trimmer Resistor with Pin Terminations, 10% 1/4W 150ppm/C")
      (fields (field (name "TOLERANCE") "10%"))
      (libsource (lib "Altium Content Vault") (part "08526ac0d5a9b3c124616c1f8dc5852"))
    )
    (comp (ref "R28")
      (value "MCU08050D1002BP100")
      (footprint "MCU08050D1002BP100:RESC2012X55N")
      (description "Res Thin Film 0805 10K Ohm 0.1% 0.125W(1/8W) Â±25ppm/C SMD Automotive Medical T/R")
      (fields (field (name "MF") "{'manufacturer': u'Vishay'}"))
      (libsource (lib "*") (part "MCU08050D1002BP100"))
    )
    (comp (ref "R29")
      (value "PV37W104C01B00")
      (footprint "FP-PV37W104C01B00-MFG")
      (description "12-Turn Through Hole Trimmer Resistor with Pin Terminations, 10% 1/4W 150ppm/C")
      (fields (field (name "TOLERANCE") "10%"))
      (libsource (lib "Altium Content Vault") (part "08526ac0d5a9b3c124616c1f8dc5852"))
    )
    (comp (ref "R30")
      (value "PV37W104C01B00")
      (footprint "FP-PV37W104C01B00-MFG")
      (description "12-Turn Through Hole Trimmer Resistor with Pin Terminations, 10% 1/4W 150ppm/C")
      (fields (field (name "TOLERANCE") "10%"))
      (libsource (lib "Altium Content Vault") (part "08526ac0d5a9b3c124616c1f8dc5852"))
    )
    (comp (ref "R31")
      (value "PV37W104C01B00")
      (footprint "FP-PV37W104C01B00-MFG")
      (description "12-Turn Through Hole Trimmer Resistor with Pin Terminations, 10% 1/4W 150ppm/C")
      (fields (field (name "TOLERANCE") "10%"))
      (libsource (lib "Altium Content Vault") (part "08526ac0d5a9b3c124616c1f8dc5852"))
    )
    (comp (ref "R32")
      (value "10K 0805")
      (footprint "RESC2013X60X35NL10T20")
      (description "Chip Resistor, 10 KOhm, +/- 1%, 0.125 W, -55 to 155 degC, 0805 (2012 Metric), RoHS, Tape and Reel")
      (fields (field (name "MANUFACTURER") "Yageo"))
      (libsource (lib "Altium Content Vault") (part "RES-2"))
    )
    (comp (ref "R33")
      (value "PV37W104C01B00")
      (footprint "FP-PV37W104C01B00-MFG")
      (description "12-Turn Through Hole Trimmer Resistor with Pin Terminations, 10% 1/4W 150ppm/C")
      (fields (field (name "TOLERANCE") "10%"))
      (libsource (lib "Altium Content Vault") (part "08526ac0d5a9b3c124616c1f8dc5852"))
    )
    (comp (ref "R34")
      (value "10K 0805")
      (footprint "RESC2013X60X35NL10T20")
      (description "Chip Resistor, 10 KOhm, +/- 1%, 0.125 W, -55 to 155 degC, 0805 (2012 Metric), RoHS, Tape and Reel")
      (fields (field (name "MANUFACTURER") "Yageo"))
      (libsource (lib "Altium Content Vault") (part "RES-2"))
    )
    (comp (ref "R35")
      (value "CRCW0603150RFKEAHP")
      (footprint "FP-CRCW0603-HPe3-MFG")
      (description "RES Thick Film, 150Ω, 1%, 0.33W, 100ppm/°C, 0603")
      (fields (field (name "TOLERANCE") "1%"))
      (libsource (lib "Altium Content Vault") (part "1029c3af85768c4190bb7ad29bc67b5"))
    )
    (comp (ref "R36")
      (value "CRCW0603150RFKEAHP")
      (footprint "FP-CRCW0603-HPe3-MFG")
      (description "RES Thick Film, 150Ω, 1%, 0.33W, 100ppm/°C, 0603")
      (fields (field (name "TOLERANCE") "1%"))
      (libsource (lib "Altium Content Vault") (part "1029c3af85768c4190bb7ad29bc67b5"))
    )
    (comp (ref "R37")
      (value "10K 0805")
      (footprint "RESC2013X60X35NL10T20")
      (description "Chip Resistor, 10 KOhm, +/- 1%, 0.125 W, -55 to 155 degC, 0805 (2012 Metric), RoHS, Tape and Reel")
      (fields (field (name "MANUFACTURER") "Yageo"))
      (libsource (lib "Altium Content Vault") (part "RES-2"))
    )
    (comp (ref "R38")
      (value "ERA3AEB561V")
      (footprint "RESC1608X55X30LL20T20")
      (fields (field (name "MANUFACTURER") "Panasonic"))
      (libsource (lib "Altium Content Vault") (part "RES"))
    )
    (comp (ref "R39")
      (value "10K 0805")
      (footprint "RESC2013X60X35NL10T20")
      (description "Chip Resistor, 10 KOhm, +/- 1%, 0.125 W, -55 to 155 degC, 0805 (2012 Metric), RoHS, Tape and Reel")
      (fields (field (name "MANUFACTURER") "Yageo"))
      (libsource (lib "Altium Content Vault") (part "RES-2"))
    )
    (comp (ref "R40")
      (value "10K 0805")
      (footprint "RESC2013X60X35NL10T20")
      (description "Chip Resistor, 10 KOhm, +/- 1%, 0.125 W, -55 to 155 degC, 0805 (2012 Metric), RoHS, Tape and Reel")
      (fields (field (name "MANUFACTURER") "Yageo"))
      (libsource (lib "Altium Content Vault") (part "RES-2"))
    )
    (comp (ref "R41")
      (value "MCU08050D2002BP500")
      (footprint "MCU08050D2002BP500:RESC2012X55N")
      (description "RES -FILM RESISTORS-THICK FILM CHIP")
      (fields (field (name "MF") "{'manufacturer': u'Vishay'}"))
      (libsource (lib "*") (part "MCU08050D2002BP500"))
    )
    (comp (ref "R42")
      (value "10K 0805")
      (footprint "RESC2013X60X35NL10T20")
      (description "Chip Resistor, 10 KOhm, +/- 1%, 0.125 W, -55 to 155 degC, 0805 (2012 Metric), RoHS, Tape and Reel")
      (fields (field (name "MANUFACTURER") "Yageo"))
      (libsource (lib "Altium Content Vault") (part "RES-2"))
    )
    (comp (ref "R43")
      (value "PV37W104C01B00")
      (footprint "FP-PV37W104C01B00-MFG")
      (description "12-Turn Through Hole Trimmer Resistor with Pin Terminations, 10% 1/4W 150ppm/C")
      (fields (field (name "TOLERANCE") "10%"))
      (libsource (lib "Altium Content Vault") (part "08526ac0d5a9b3c124616c1f8dc5852"))
    )
    (comp (ref "R44")
      (value "10K 0805")
      (footprint "RESC2013X60X35NL10T20")
      (description "Chip Resistor, 10 KOhm, +/- 1%, 0.125 W, -55 to 155 degC, 0805 (2012 Metric), RoHS, Tape and Reel")
      (fields (field (name "MANUFACTURER") "Yageo"))
      (libsource (lib "Altium Content Vault") (part "RES-2"))
    )
    (comp (ref "R45")
      (value "ERA3AEB561V")
      (footprint "RESC1608X55X30LL20T20")
      (fields (field (name "MANUFACTURER") "Panasonic"))
      (libsource (lib "Altium Content Vault") (part "RES"))
    )
    (comp (ref "R46")
      (value "10K 0805")
      (footprint "RESC2013X60X35NL10T20")
      (description "Chip Resistor, 10 KOhm, +/- 1%, 0.125 W, -55 to 155 degC, 0805 (2012 Metric), RoHS, Tape and Reel")
      (fields (field (name "MANUFACTURER") "Yageo"))
      (libsource (lib "Altium Content Vault") (part "RES-2"))
    )
    (comp (ref "R47")
      (value "10K 0805")
      (footprint "RESC2013X60X35NL10T20")
      (description "Chip Resistor, 10 KOhm, +/- 1%, 0.125 W, -55 to 155 degC, 0805 (2012 Metric), RoHS, Tape and Reel")
      (fields (field (name "MANUFACTURER") "Yageo"))
      (libsource (lib "Altium Content Vault") (part "RES-2"))
    )
    (comp (ref "R48")
      (value "10K 0805")
      (footprint "RESC2013X60X35NL10T20")
      (description "Chip Resistor, 10 KOhm, +/- 1%, 0.125 W, -55 to 155 degC, 0805 (2012 Metric), RoHS, Tape and Reel")
      (fields (field (name "MANUFACTURER") "Yageo"))
      (libsource (lib "Altium Content Vault") (part "RES-2"))
    )
    (comp (ref "R49")
      (value "10K 0805")
      (footprint "RESC2013X60X35NL10T20")
      (description "Chip Resistor, 10 KOhm, +/- 1%, 0.125 W, -55 to 155 degC, 0805 (2012 Metric), RoHS, Tape and Reel")
      (fields (field (name "MANUFACTURER") "Yageo"))
      (libsource (lib "Altium Content Vault") (part "RES-2"))
    )
    (comp (ref "R50")
      (value "10K 0805")
      (footprint "RESC2013X60X35NL10T20")
      (description "Chip Resistor, 10 KOhm, +/- 1%, 0.125 W, -55 to 155 degC, 0805 (2012 Metric), RoHS, Tape and Reel")
      (fields (field (name "MANUFACTURER") "Yageo"))
      (libsource (lib "Altium Content Vault") (part "RES-2"))
    )
    (comp (ref "RE1")
      (value "4682 / 1528-4682-ND")
      (footprint "SDCARD")
      (description "MICROSD SPI/SPIO BREAKOUT BOARD")
      (fields
        (field (name "MANUFACTURER") "Adafruit Industries")
        (field (name "MANUFACTURER PART NUMBER") "4682")
      )
      (libsource (lib "PedalControl") (part "4682"))
    )
    (comp (ref "U1")
      (value "SN74LVC2G08IDCTRQ1")
      (footprint "DCT0008A_N")
      (description "Automotive Catalog Dual 2-Input Positive-AND Gate, DCT0008A, LARGE T&R")
      (fields
        (field (name "MANUFACTURER") "Texas Instruments")
        (field (name "GENERIC PART NUMBER") "SN74LVC2G08-Q1")
      )
      (libsource (lib "Altium Content Vault") (part "TI-SN74XXX2G08-8"))
    )
    (comp (ref "U2")
      (value "SN74LVC2G32DCTR")
      (footprint "FP-DCT0008A-MFG")
      (description "IC GATE OR 2CH 2-INP SM8")
      (fields
        (field (name "OCTOPART") "https://octopart.com/sn74lvc2g32dctr-texas+instruments-464565")
        (field (name "MANUFACTURER") "Texas Instruments")
      )
      (libsource (lib "Altium Content Vault") (part "47fc598a8b1d4a01438179770b2ee6a"))
    )
    (comp (ref "U3")
      (value "SN74LVC1G11DBVR")
      (footprint "DBV0006A_N")
      (description "Single 3-Input Positive-AND Gate, DBV0006A, LARGE T&R")
      (fields
        (field (name "MANUFACTURER") "Texas Instruments")
        (field (name "GENERIC PART NUMBER") "SN74LVC1G11")
      )
      (libsource (lib "Altium Content Vault") (part "TI-AND-1-3IN-6"))
    )
    (comp (ref "U4")
      (value "CD40109BQNSRQ1")
      (footprint "FP-NS0016A-IPC_C")
      (description "IC TRNSLTR UNIDIRECTIONAL 16SO")
      (libsource (lib "Altium Content Vault") (part "478688682dd803327ab49bead7bebe6"))
    )
    (comp (ref "U5")
      (value "TLV9102IDR")
      (footprint "FP-D0008A-IPC_B")
      (description "IC OPAMP POWER 2 CIRCUIT 8SOIC")
      (libsource (lib "Altium Content Vault") (part "d5b36c1049528187b1d2197d5d58d7e"))
    )
    (comp (ref "U6")
      (value "TLV9102IDR")
      (footprint "FP-D0008A-IPC_B")
      (description "IC OPAMP POWER 2 CIRCUIT 8SOIC")
      (libsource (lib "Altium Content Vault") (part "d5b36c1049528187b1d2197d5d58d7e"))
    )
    (comp (ref "U7")
      (value "MCP2551-I/SN")
      (footprint "MCHP-SN8_V")
      (fields (field (name "MANUFACTURER") "Microchip"))
      (libsource (lib "Altium Content Vault") (part "MCHP-MCP2551-SN8"))
    )
    (comp (ref "U8")
      (value "TLV9102IDR")
      (footprint "FP-D0008A-IPC_B")
      (description "IC OPAMP POWER 2 CIRCUIT 8SOIC")
      (libsource (lib "Altium Content Vault") (part "d5b36c1049528187b1d2197d5d58d7e"))
    )
    (comp (ref "U9")
      (value "NUCLEO-F446RE")
      (footprint "MODULE_NUCLEO-F446RE")
      (fields (field (name "MF") "{'manufacturer': u'STMicroelectronics'}"))
      (libsource (lib "SnapEDA_Library") (part "NUCLEO-F446RE"))
    )
    (comp (ref "U10")
      (value "TLV9102IDR")
      (footprint "FP-D0008A-IPC_B")
      (description "IC OPAMP POWER 2 CIRCUIT 8SOIC")
      (libsource (lib "Altium Content Vault") (part "d5b36c1049528187b1d2197d5d58d7e"))
    )
    (comp (ref "U11")
      (value "ADP7142ARDZ-5.0")
      (footprint "FP-RD-8-1-IPC_B")
      (description "IC REG LINEAR 5V 200MA 8SOIC")
      (libsource (lib "Altium Content Vault") (part "5376f2dc61542934a6ea64a46ad4087"))
    )
    (comp (ref "U12")
      (value "SN74LVC1G11DBVR")
      (footprint "DBV0006A_N")
      (description "Single 3-Input Positive-AND Gate, DBV0006A, LARGE T&R")
      (fields
        (field (name "MANUFACTURER") "Texas Instruments")
        (field (name "GENERIC PART NUMBER") "SN74LVC1G11")
      )
      (libsource (lib "Altium Content Vault") (part "TI-AND-1-3IN-6"))
    )
    (comp (ref "U16")
      (value "Optoisolator1")
      (footprint "FOD852")
      (description "4-Pin Phototransistor Optocoupler")
      (fields (field (name "PUBLISHER") "Altium Limited"))
      (libsource (lib "Miscellaneous Devices") (part "Optoisolator1"))
    )
    (comp (ref "U19")
      (value "LM2903D")
      (footprint "FP-SO8-IPC_C")
      (description "IC COMPARATOR DUAL LP 8-SOIC")
      (fields
        (field (name "MANUFACTURER") "STMicroelectronics")
        (field (name "OCTOPART") "https://octopart.com/lm2903d-stmicroelectronics-428759")
      )
      (libsource (lib "Altium Content Vault") (part "9f386d5a0a155305257da89b0c2f71e"))
    )
    (comp (ref "U22")
      (value "LM2903D")
      (footprint "FP-SO8-IPC_C")
      (description "IC COMPARATOR DUAL LP 8-SOIC")
      (fields
        (field (name "MANUFACTURER") "STMicroelectronics")
        (field (name "OCTOPART") "https://octopart.com/lm2903d-stmicroelectronics-428759")
      )
      (libsource (lib "Altium Content Vault") (part "9f386d5a0a155305257da89b0c2f71e"))
    )
    (comp (ref "U23")
      (value "Optoisolator1")
      (footprint "FOD852")
      (description "4-Pin Phototransistor Optocoupler")
      (fields (field (name "PUBLISHER") "Altium Limited"))
      (libsource (lib "Miscellaneous Devices") (part "Optoisolator1"))
    )
    (comp (ref "U26")
      (value "LM2903D")
      (footprint "FP-SO8-IPC_C")
      (description "IC COMPARATOR DUAL LP 8-SOIC")
      (fields
        (field (name "MANUFACTURER") "STMicroelectronics")
        (field (name "OCTOPART") "https://octopart.com/lm2903d-stmicroelectronics-428759")
      )
      (libsource (lib "Altium Content Vault") (part "9f386d5a0a155305257da89b0c2f71e"))
    )
    (comp (ref "U30")
      (value "LM2903D")
      (footprint "FP-SO8-IPC_C")
      (description "IC COMPARATOR DUAL LP 8-SOIC")
      (fields
        (field (name "MANUFACTURER") "STMicroelectronics")
        (field (name "OCTOPART") "https://octopart.com/lm2903d-stmicroelectronics-428759")
      )
      (libsource (lib "Altium Content Vault") (part "9f386d5a0a155305257da89b0c2f71e"))
    )
  )
  (nets
    (net (code "1") (name "+3.3") (class "Default")
      (node (ref "RE1") (pin "9") (pinfunction "3V_9") (pintype "input"))
      (node (ref "U4") (pin "16") (pinfunction "VDD_16") (pintype "power_in"))
      (node (ref "U9") (pin "CN7_16") (pinfunction "CN7_+3V3_CN7_16") (pintype "power_in"))
    )
    (net (code "2") (name "+5") (class "Default")
      (node (ref "C5") (pin "1") (pinfunction "1_1") (pintype "passive"))
      (node (ref "I/O 1") (pin "11") (pintype "passive"))
      (node (ref "I/O 2") (pin "1") (pintype "passive"))
      (node (ref "I/O 2") (pin "12") (pintype "passive"))
      (node (ref "I/O 2") (pin "6") (pintype "passive"))
      (node (ref "Pedals") (pin "1") (pintype "passive"))
      (node (ref "Pedals") (pin "4") (pintype "passive"))
      (node (ref "Pedals") (pin "7") (pintype "passive"))
      (node (ref "Q2") (pin "2") (pinfunction "SOURCE_2") (pintype "passive"))
      (node (ref "R11") (pin "2") (pinfunction "2_2") (pintype "passive"))
      (node (ref "R16") (pin "2") (pinfunction "2_2") (pintype "passive"))
      (node (ref "R2") (pin "1") (pinfunction "1_1") (pintype "passive"))
      (node (ref "R24") (pin "2") (pinfunction "2_2") (pintype "passive"))
      (node (ref "R42") (pin "2") (pinfunction "2_2") (pintype "passive"))
      (node (ref "R6") (pin "2") (pinfunction "2_2") (pintype "passive"))
      (node (ref "R7") (pin "2") (pinfunction "2_2") (pintype "passive"))
      (node (ref "R8") (pin "2") (pinfunction "2_2") (pintype "passive"))
      (node (ref "R9") (pin "2") (pinfunction "2_2") (pintype "passive"))
      (node (ref "U1") (pin "8") (pinfunction "VCC_8") (pintype "power_in"))
      (node (ref "U10") (pin "8") (pinfunction "V+_8") (pintype "power_in"))
      (node (ref "U12") (pin "5") (pinfunction "VCC_5") (pintype "power_in"))
      (node (ref "U19") (pin "8") (pinfunction "VCC+_8") (pintype "power_in"))
      (node (ref "U2") (pin "8") (pinfunction "VCC_8") (pintype "power_in"))
      (node (ref "U22") (pin "8") (pinfunction "VCC+_8") (pintype "power_in"))
      (node (ref "U26") (pin "8") (pinfunction "VCC+_8") (pintype "power_in"))
      (node (ref "U3") (pin "5") (pinfunction "VCC_5") (pintype "power_in"))
      (node (ref "U4") (pin "1") (pinfunction "VCC_1") (pintype "power_in"))
      (node (ref "U4") (pin "15") (pinfunction "ENABLE_D_15") (pintype "input"))
      (node (ref "U4") (pin "2") (pinfunction "ENABLE_A_2") (pintype "input"))
      (node (ref "U4") (pin "7") (pinfunction "ENABLE_B_7") (pintype "input"))
      (node (ref "U4") (pin "9") (pinfunction "ENABLE_C_9") (pintype "input"))
      (node (ref "U5") (pin "8") (pinfunction "V+_8") (pintype "power_in"))
      (node (ref "U6") (pin "8") (pinfunction "V+_8") (pintype "power_in"))
      (node (ref "U7") (pin "3") (pinfunction "VDD_3") (pintype "power_in"))
      (node (ref "U8") (pin "8") (pinfunction "V+_8") (pintype "power_in"))
      (node (ref "U9") (pin "CN7_18") (pinfunction "CN7_+5V_CN7_18") (pintype "power_in"))
    )
    (net (code "3") (name "+5_REF") (class "Default")
      (node (ref "C20") (pin "1") (pinfunction "1_1") (pintype "passive"))
      (node (ref "C28") (pin "1") (pinfunction "1_1") (pintype "passive"))
      (node (ref "C34") (pin "1") (pinfunction "1_1") (pintype "passive"))
      (node (ref "C42") (pin "1") (pinfunction "1_1") (pintype "passive"))
      (node (ref "C43") (pin "1") (pinfunction "1_1") (pintype "passive"))
      (node (ref "C50") (pin "1") (pinfunction "1_1") (pintype "passive"))
      (node (ref "C52") (pin "1") (pinfunction "1_1") (pintype "passive"))
      (node (ref "C6") (pin "1") (pinfunction "1_1") (pintype "passive"))
      (node (ref "C8") (pin "1") (pinfunction "1_1") (pintype "passive"))
      (node (ref "R12") (pin "3") (pinfunction "3_3") (pintype "passive"))
      (node (ref "R22") (pin "3") (pinfunction "3_3") (pintype "passive"))
      (node (ref "R27") (pin "3") (pinfunction "3_3") (pintype "passive"))
      (node (ref "R29") (pin "3") (pinfunction "3_3") (pintype "passive"))
      (node (ref "R30") (pin "3") (pinfunction "3_3") (pintype "passive"))
      (node (ref "R31") (pin "3") (pinfunction "3_3") (pintype "passive"))
      (node (ref "R33") (pin "3") (pinfunction "3_3") (pintype "passive"))
      (node (ref "R43") (pin "3") (pinfunction "3_3") (pintype "passive"))
      (node (ref "U11") (pin "1") (pinfunction "VOUT_1") (pintype "passive"))
      (node (ref "U11") (pin "2") (pinfunction "VOUT_2") (pintype "passive"))
      (node (ref "U11") (pin "3") (pinfunction "SENSE/ADJ_3") (pintype "passive"))
    )
    (net (code "4") (name "+12") (class "Default")
      (node (ref "C10") (pin "1") (pinfunction "1_1") (pintype "passive"))
      (node (ref "C3") (pin "1") (pinfunction "1_1") (pintype "passive"))
      (node (ref "I/O 1") (pin "1") (pintype "passive"))
      (node (ref "Q1") (pin "2") (pinfunction "SOURCE_2") (pintype "passive"))
      (node (ref "Q3") (pin "2") (pinfunction "SOURCE_2") (pintype "passive"))
      (node (ref "R14") (pin "2") (pinfunction "2_2") (pintype "passive"))
      (node (ref "R37") (pin "2") (pinfunction "2_2") (pintype "passive"))
      (node (ref "R39") (pin "1") (pinfunction "1_1") (pintype "passive"))
      (node (ref "U11") (pin "5") (pinfunction "EN_5") (pintype "input"))
      (node (ref "U11") (pin "7") (pinfunction "VIN_7") (pintype "power_in"))
      (node (ref "U11") (pin "8") (pinfunction "VIN_8") (pintype "power_in"))
      (node (ref "U16") (pin "4") (pinfunction "C_4") (pintype "passive"))
      (node (ref "U23") (pin "4") (pinfunction "C_4") (pintype "passive"))
      (node (ref "U30") (pin "8") (pinfunction "VCC+_8") (pintype "power_in"))
    )
    (net (code "5") (name "/!Brake_Signal") (class "Default")
      (node (ref "Q2") (pin "3") (pinfunction "DRAIN_3") (pintype "passive"))
      (node (ref "R17") (pin "2") (pinfunction "2_2") (pintype "passive"))
    )
    (net (code "6") (name "/!Hard Brake") (class "Default")
      (node (ref "Q3") (pin "1") (pinfunction "GATE_1") (pintype "passive"))
      (node (ref "R42") (pin "1") (pinfunction "1_1") (pintype "passive"))
      (node (ref "U2") (pin "2") (pinfunction "1B_2") (pintype "input"))
      (node (ref "U30") (pin "7") (pinfunction "Out2_7") (pintype "passive"))
      (node (ref "U9") (pin "CN10_13") (pinfunction "PA6_CN10_13") (pintype "bidirectional"))
    )
    (net (code "7") (name "/APPS OK MCU") (class "Default")
      (node (ref "U16") (pin "2") (pinfunction "K_2") (pintype "passive"))
      (node (ref "U9") (pin "CN10_19") (pinfunction "PC7_CN10_19") (pintype "bidirectional"))
    )
    (net (code "8") (name "/APPS1") (class "Default")
      (node (ref "R15") (pin "1") (pinfunction "1_1") (pintype "passive"))
      (node (ref "R18") (pin "2") (pinfunction "2_2") (pintype "passive"))
      (node (ref "U9") (pin "CN7_38") (pinfunction "PC0/PB8_CN7_38") (pintype "bidirectional"))
    )
    (net (code "9") (name "/APPS1_IN") (class "Default")
      (node (ref "APPS1") (pin "1") (pintype "passive"))
      (node (ref "R34") (pin "1") (pinfunction "1_1") (pintype "passive"))
    )
    (net (code "10") (name "/APPS2") (class "Default")
      (node (ref "R19") (pin "1") (pinfunction "1_1") (pintype "passive"))
      (node (ref "R26") (pin "2") (pinfunction "2_2") (pintype "passive"))
      (node (ref "U9") (pin "CN7_36") (pinfunction "PC1/PB9_CN7_36") (pintype "bidirectional"))
    )
    (net (code "11") (name "/APPS2_IN") (class "Default")
      (node (ref "APPS2") (pin "1") (pintype "passive"))
      (node (ref "R23") (pin "1") (pinfunction "1_1") (pintype "passive"))
    )
    (net (code "12") (name "/APPS_OK") (class "Default")
      (node (ref "K1") (pin "7") (pinfunction "7_7") (pintype "passive"))
      (node (ref "K2") (pin "2") (pinfunction "2_2") (pintype "passive"))
      (node (ref "U16") (pin "3") (pinfunction "E_3") (pintype "passive"))
    )
    (net (code "13") (name "/BRAKE_LIGHT_POS") (class "Default")
      (node (ref "D12") (pin "2") (pinfunction "A_2") (pintype "passive"))
      (node (ref "I/O 1") (pin "2") (pintype "passive"))
      (node (ref "Q1") (pin "3") (pinfunction "DRAIN_3") (pintype "passive"))
    )
    (net (code "14") (name "/BSE H") (class "Default")
      (node (ref "R30") (pin "2") (pinfunction "2_2") (pintype "passive"))
      (node (ref "U26") (pin "3") (pinfunction "In1+_3") (pintype "tri_state"))
    )
    (net (code "15") (name "/BSE L") (class "Default")
      (node (ref "R27") (pin "2") (pinfunction "2_2") (pintype "passive"))
      (node (ref "U22") (pin "2") (pinfunction "In1-_2") (pintype "tri_state"))
    )
    (net (code "16") (name "/BSE_Filtered") (class "Default")
      (node (ref "Brake Invert") (pin "1") (pinfunction "1_1") (pintype "passive"))
      (node (ref "Brake invert2") (pin "3") (pinfunction "3_3") (pintype "passive"))
      (node (ref "C51") (pin "1") (pinfunction "1_1") (pintype "passive"))
      (node (ref "HBrake Invert1") (pin "1") (pinfunction "1_1") (pintype "passive"))
      (node (ref "Hvy Brk Inv") (pin "3") (pinfunction "3_3") (pintype "passive"))
      (node (ref "R32") (pin "2") (pinfunction "2_2") (pintype "passive"))
      (node (ref "U22") (pin "3") (pinfunction "In1+_3") (pintype "tri_state"))
      (node (ref "U26") (pin "2") (pinfunction "In1-_2") (pintype "tri_state"))
    )
    (net (code "17") (name "/BSE_IN") (class "Default")
      (node (ref "BSE") (pin "2") (pintype "passive"))
      (node (ref "R32") (pin "1") (pinfunction "1_1") (pintype "passive"))
    )
    (net (code "18") (name "/BSPD DLY") (class "Default")
      (node (ref "R22") (pin "2") (pinfunction "2_2") (pintype "passive"))
      (node (ref "U19") (pin "6") (pinfunction "In2-_6") (pintype "tri_state"))
    )
    (net (code "19") (name "/BSPD_FAIL") (class "Default")
      (node (ref "Q5") (pin "3") (pinfunction "D_3") (pintype "passive"))
      (node (ref "R39") (pin "2") (pinfunction "2_2") (pintype "passive"))
      (node (ref "U9") (pin "CN10_2") (pinfunction "PC8_CN10_2") (pintype "bidirectional"))
    )
    (net (code "20") (name "/CANH") (class "Default")
      (node (ref "I/O 2") (pin "8") (pintype "passive"))
      (node (ref "U7") (pin "7") (pinfunction "CANH_7") (pintype "bidirectional"))
    )
    (net (code "21") (name "/CANL") (class "Default")
      (node (ref "I/O 2") (pin "7") (pintype "passive"))
      (node (ref "U7") (pin "6") (pinfunction "CANL_6") (pintype "bidirectional"))
    )
    (net (code "22") (name "/CAN_RX") (class "Default")
      (node (ref "U7") (pin "4") (pinfunction "RXD_4") (pintype "output"))
      (node (ref "U9") (pin "CN10_14") (pinfunction "PA11_CN10_14") (pintype "bidirectional"))
    )
    (net (code "23") (name "/CAN_TX") (class "Default")
      (node (ref "U7") (pin "1") (pinfunction "TXD_1") (pintype "input"))
      (node (ref "U9") (pin "CN10_12") (pinfunction "PA12_CN10_12") (pintype "bidirectional"))
    )
    (net (code "24") (name "/CUR H") (class "Default")
      (node (ref "R33") (pin "2") (pinfunction "2_2") (pintype "passive"))
      (node (ref "U26") (pin "5") (pinfunction "In2+_5") (pintype "tri_state"))
    )
    (net (code "25") (name "/CUR L") (class "Default")
      (node (ref "R29") (pin "2") (pinfunction "2_2") (pintype "passive"))
      (node (ref "U22") (pin "6") (pinfunction "In2-_6") (pintype "tri_state"))
    )
    (net (code "26") (name "/CURRENT_SENSOR") (class "Default")
      (node (ref "Current Sensor Inverted Select") (pin "1") (pinfunction "1_1") (pintype "passive"))
      (node (ref "Current Sensor Inverted Select2") (pin "3") (pinfunction "3_3") (pintype "passive"))
      (node (ref "U22") (pin "5") (pinfunction "In2+_5") (pintype "tri_state"))
      (node (ref "U26") (pin "6") (pinfunction "In2-_6") (pintype "tri_state"))
      (node (ref "U8") (pin "1") (pinfunction "OUT1_1") (pintype "passive"))
      (node (ref "U8") (pin "3") (pinfunction "IN1+_3") (pintype "tri_state"))
    )
    (net (code "27") (name "/CURRENT_SENSOR_IN") (class "Default")
      (node (ref "I/O 1") (pin "4") (pintype "passive"))
      (node (ref "R5") (pin "1") (pinfunction "1_1") (pintype "passive"))
    )
    (net (code "28") (name "/Drive Switch") (class "Default")
      (node (ref "I/O 1") (pin "3") (pintype "passive"))
      (node (ref "R46") (pin "2") (pinfunction "2_2") (pintype "passive"))
    )
    (net (code "29") (name "/FL_Encoder") (class "Default")
      (node (ref "U4") (pin "5") (pinfunction "F_5") (pintype "output"))
      (node (ref "U9") (pin "CN7_30") (pinfunction "PA1_CN7_30") (pintype "bidirectional"))
    )
    (net (code "30") (name "/FL_Encoder_IN") (class "Default")
      (node (ref "I/O 2") (pin "11") (pintype "passive"))
      (node (ref "U4") (pin "6") (pinfunction "B_6") (pintype "input"))
    )
    (net (code "31") (name "/FR_Encoder") (class "Default")
      (node (ref "U4") (pin "4") (pinfunction "E_4") (pintype "output"))
      (node (ref "U9") (pin "CN7_28") (pinfunction "PA0_CN7_28") (pintype "bidirectional"))
    )
    (net (code "32") (name "/FR_Encoder_IN") (class "Default")
      (node (ref "I/O 2") (pin "5") (pintype "passive"))
      (node (ref "U4") (pin "3") (pinfunction "A_3") (pintype "input"))
    )
    (net (code "33") (name "/Hard Brake") (class "Default")
      (node (ref "Q3") (pin "3") (pinfunction "DRAIN_3") (pintype "passive"))
      (node (ref "R45") (pin "2") (pinfunction "2_2") (pintype "passive"))
      (node (ref "R47") (pin "2") (pinfunction "2_2") (pintype "passive"))
    )
    (net (code "34") (name "/Left Throttle") (class "Default")
      (node (ref "U5") (pin "5") (pinfunction "IN2+_5") (pintype "tri_state"))
      (node (ref "U9") (pin "CN10_11") (pinfunction "PA5_CN10_11") (pintype "bidirectional"))
    )
    (net (code "35") (name "/Left Throttle 5V") (class "Default")
      (node (ref "I/O 1") (pin "8") (pintype "passive"))
      (node (ref "R10") (pin "2") (pinfunction "2_2") (pintype "passive"))
      (node (ref "U5") (pin "7") (pinfunction "OUT2_7") (pintype "passive"))
    )
    (net (code "36") (name "/OUT7") (class "Default")
      (node (ref "Brake Invert") (pin "3") (pinfunction "3_3") (pintype "passive"))
      (node (ref "Brake invert2") (pin "1") (pinfunction "1_1") (pintype "passive"))
      (node (ref "R31") (pin "2") (pinfunction "2_2") (pintype "passive"))
    )
    (net (code "37") (name "/OUT8") (class "Default")
      (node (ref "HBrake Invert1") (pin "3") (pinfunction "3_3") (pintype "passive"))
      (node (ref "Hvy Brk Inv") (pin "1") (pinfunction "1_1") (pintype "passive"))
      (node (ref "R43") (pin "2") (pinfunction "2_2") (pintype "passive"))
    )
    (net (code "38") (name "/PLAUSIBILTY_CHECK") (class "Default")
      (node (ref "R20") (pin "2") (pinfunction "2_2") (pintype "passive"))
      (node (ref "U2") (pin "3") (pinfunction "2Y_3") (pintype "output"))
      (node (ref "U3") (pin "1") (pinfunction "A_1") (pintype "input"))
    )
    (net (code "39") (name "/Ready To Drive Sound") (class "Default")
      (node (ref "I/O 2") (pin "10") (pintype "passive"))
      (node (ref "Q4") (pin "3") (pinfunction "D_3") (pintype "passive"))
    )
    (net (code "40") (name "/Right Throttle") (class "Default")
      (node (ref "U5") (pin "3") (pinfunction "IN1+_3") (pintype "tri_state"))
      (node (ref "U9") (pin "CN7_32") (pinfunction "PA4_CN7_32") (pintype "bidirectional"))
    )
    (net (code "41") (name "/Right Throttle 5V") (class "Default")
      (node (ref "I/O 1") (pin "9") (pintype "passive"))
      (node (ref "R1") (pin "2") (pinfunction "2_2") (pintype "passive"))
      (node (ref "U5") (pin "1") (pinfunction "OUT1_1") (pintype "passive"))
    )
    (net (code "42") (name "/SD_CLK") (class "Default")
      (node (ref "RE1") (pin "7") (pinfunction "CLK_7") (pintype "input"))
      (node (ref "U9") (pin "CN10_31") (pinfunction "PB3_CN10_31") (pintype "bidirectional"))
    )
    (net (code "43") (name "/SD_CMD") (class "Default")
      (node (ref "RE1") (pin "5") (pinfunction "CMD/S1_5") (pintype "input"))
      (node (ref "U9") (pin "CN10_15") (pinfunction "PA7_CN10_15") (pintype "bidirectional"))
    )
    (net (code "44") (name "/SD_D1") (class "Default")
      (node (ref "RE1") (pin "3") (pinfunction "D1_3") (pintype "input"))
      (node (ref "U9") (pin "CN10_1") (pinfunction "PC9_CN10_1") (pintype "bidirectional"))
    )
    (net (code "45") (name "/SD_DAT2") (class "Default")
      (node (ref "RE1") (pin "2") (pinfunction "DAT2_2") (pintype "input"))
    )
    (net (code "46") (name "/SD_DET") (class "Default")
      (node (ref "RE1") (pin "1") (pinfunction "DET_1") (pintype "input"))
      (node (ref "U9") (pin "CN10_17") (pinfunction "PB6_CN10_17") (pintype "bidirectional"))
    )
    (net (code "47") (name "/SENSOR OVER CHECK") (class "Default")
      (node (ref "R36") (pin "2") (pinfunction "2_2") (pintype "passive"))
      (node (ref "U1") (pin "3") (pinfunction "2Y_3") (pintype "output"))
      (node (ref "U3") (pin "6") (pinfunction "C_6") (pintype "input"))
    )
    (net (code "48") (name "/SENSOR UNDER CHECK") (class "Default")
      (node (ref "R35") (pin "2") (pinfunction "2_2") (pintype "passive"))
      (node (ref "U1") (pin "7") (pinfunction "1Y_7") (pintype "output"))
      (node (ref "U3") (pin "3") (pinfunction "B_3") (pintype "input"))
    )
    (net (code "49") (name "/SSC") (class "Default")
      (node (ref "K1") (pin "2") (pinfunction "2_2") (pintype "passive"))
      (node (ref "K3") (pin "1") (pinfunction "1_1") (pintype "passive"))
    )
    (net (code "50") (name "/SSC_END") (class "Default")
      (node (ref "I/O 1") (pin "5") (pintype "passive"))
      (node (ref "R44") (pin "2") (pinfunction "2_2") (pintype "passive"))
    )
    (net (code "51") (name "/SSC_IN") (class "Default")
      (node (ref "I/O 1") (pin "6") (pintype "passive"))
      (node (ref "K1") (pin "1") (pinfunction "1_1") (pintype "passive"))
    )
    (net (code "52") (name "/SSC_OUT") (class "Default")
      (node (ref "I/O 1") (pin "12") (pintype "passive"))
      (node (ref "K3") (pin "2") (pinfunction "2_2") (pintype "passive"))
    )
    (net (code "53") (name "/SSC_RESET") (class "Default")
      (node (ref "D2") (pin "2") (pinfunction "K_2") (pintype "passive"))
      (node (ref "D4") (pin "2") (pinfunction "K_2") (pintype "passive"))
      (node (ref "I/O 1") (pin "10") (pintype "passive"))
      (node (ref "K2") (pin "8") (pinfunction "8_8") (pintype "passive"))
      (node (ref "K4") (pin "8") (pinfunction "8_8") (pintype "passive"))
    )
    (net (code "54") (name "/Steering Angle") (class "Default")
      (node (ref "I/O 2") (pin "2") (pintype "passive"))
      (node (ref "R40") (pin "1") (pinfunction "1_1") (pintype "passive"))
    )
    (net (code "55") (name "/Steering Angle 3.3V") (class "Default")
      (node (ref "R28") (pin "1") (pinfunction "1_1") (pintype "passive"))
      (node (ref "R41") (pin "2") (pinfunction "2_2") (pintype "passive"))
      (node (ref "U9") (pin "CN7_35") (pinfunction "PC2_CN7_35") (pintype "bidirectional"))
    )
    (net (code "56") (name "/TRIP CUR") (class "Default")
      (node (ref "Current Sensor Inverted Select") (pin "3") (pinfunction "3_3") (pintype "passive"))
      (node (ref "Current Sensor Inverted Select2") (pin "1") (pinfunction "1_1") (pintype "passive"))
      (node (ref "R12") (pin "2") (pinfunction "2_2") (pintype "passive"))
    )
    (net (code "57") (name "/VLOGIC") (class "Default")
      (node (ref "R25") (pin "1") (pinfunction "1_1") (pintype "passive"))
      (node (ref "U2") (pin "5") (pinfunction "2A_5") (pintype "input"))
      (node (ref "U2") (pin "7") (pinfunction "1Y_7") (pintype "output"))
    )
    (net (code "58") (name "GND") (class "Default")
      (node (ref "C1") (pin "2") (pinfunction "2_2") (pintype "passive"))
      (node (ref "C10") (pin "2") (pinfunction "2_2") (pintype "passive"))
      (node (ref "C11") (pin "2") (pinfunction "2_2") (pintype "passive"))
      (node (ref "C2") (pin "2") (pinfunction "2_2") (pintype "passive"))
      (node (ref "C20") (pin "2") (pinfunction "2_2") (pintype "passive"))
      (node (ref "C24") (pin "2") (pinfunction "2_2") (pintype "passive"))
      (node (ref "C28") (pin "2") (pinfunction "2_2") (pintype "passive"))
      (node (ref "C29") (pin "2") (pinfunction "2_2") (pintype "passive"))
      (node (ref "C3") (pin "2") (pinfunction "2_2") (pintype "passive"))
      (node (ref "C30") (pin "1") (pinfunction "1_1") (pintype "passive"))
      (node (ref "C34") (pin "2") (pinfunction "2_2") (pintype "passive"))
      (node (ref "C4") (pin "2") (pinfunction "2_2") (pintype "passive"))
      (node (ref "C42") (pin "2") (pinfunction "2_2") (pintype "passive"))
      (node (ref "C43") (pin "2") (pinfunction "2_2") (pintype "passive"))
      (node (ref "C5") (pin "2") (pinfunction "2_2") (pintype "passive"))
      (node (ref "C50") (pin "2") (pinfunction "2_2") (pintype "passive"))
      (node (ref "C51") (pin "2") (pinfunction "2_2") (pintype "passive"))
      (node (ref "C52") (pin "2") (pinfunction "2_2") (pintype "passive"))
      (node (ref "C6") (pin "2") (pinfunction "2_2") (pintype "passive"))
      (node (ref "C7") (pin "2") (pinfunction "2_2") (pintype "passive"))
      (node (ref "C8") (pin "2") (pinfunction "2_2") (pintype "passive"))
      (node (ref "D1") (pin "1") (pinfunction "A_1") (pintype "passive"))
      (node (ref "D10") (pin "1") (pinfunction "C_1") (pintype "passive"))
      (node (ref "D11") (pin "1") (pinfunction "C_1") (pintype "passive"))
      (node (ref "D2") (pin "1") (pinfunction "A_1") (pintype "passive"))
      (node (ref "D3") (pin "1") (pinfunction "A_1") (pintype "passive"))
      (node (ref "D4") (pin "1") (pinfunction "A_1") (pintype "passive"))
      (node (ref "D5") (pin "1") (pinfunction "C_1") (pintype "passive"))
      (node (ref "D7") (pin "1") (pinfunction "C_1") (pintype "passive"))
      (node (ref "D8") (pin "1") (pinfunction "C_1") (pintype "passive"))
      (node (ref "D9") (pin "1") (pinfunction "C_1") (pintype "passive"))
      (node (ref "I/O 1") (pin "7") (pintype "passive"))
      (node (ref "I/O 2") (pin "3") (pintype "passive"))
      (node (ref "I/O 2") (pin "4") (pintype "passive"))
      (node (ref "I/O 2") (pin "9") (pintype "passive"))
      (node (ref "K1") (pin "5") (pinfunction "5_5") (pintype "passive"))
      (node (ref "K2") (pin "5") (pinfunction "5_5") (pintype "passive"))
      (node (ref "K3") (pin "5") (pinfunction "5_5") (pintype "passive"))
      (node (ref "K4") (pin "5") (pinfunction "5_5") (pintype "passive"))
      (node (ref "Pedals") (pin "10") (pintype "passive"))
      (node (ref "Pedals") (pin "3") (pintype "passive"))
      (node (ref "Pedals") (pin "6") (pintype "passive"))
      (node (ref "Pedals") (pin "9") (pintype "passive"))
      (node (ref "Q4") (pin "2") (pinfunction "S_2") (pintype "passive"))
      (node (ref "Q5") (pin "2") (pinfunction "S_2") (pintype "passive"))
      (node (ref "R12") (pin "1") (pinfunction "1_1") (pintype "passive"))
      (node (ref "R13") (pin "1") (pinfunction "1_1") (pintype "passive"))
      (node (ref "R17") (pin "1") (pinfunction "1_1") (pintype "passive"))
      (node (ref "R18") (pin "1") (pinfunction "1_1") (pintype "passive"))
      (node (ref "R21") (pin "1") (pinfunction "1_1") (pintype "passive"))
      (node (ref "R22") (pin "1") (pinfunction "1_1") (pintype "passive"))
      (node (ref "R26") (pin "1") (pinfunction "1_1") (pintype "passive"))
      (node (ref "R27") (pin "1") (pinfunction "1_1") (pintype "passive"))
      (node (ref "R29") (pin "1") (pinfunction "1_1") (pintype "passive"))
      (node (ref "R30") (pin "1") (pinfunction "1_1") (pintype "passive"))
      (node (ref "R31") (pin "1") (pinfunction "1_1") (pintype "passive"))
      (node (ref "R33") (pin "1") (pinfunction "1_1") (pintype "passive"))
      (node (ref "R38") (pin "1") (pinfunction "1_1") (pintype "passive"))
      (node (ref "R4") (pin "1") (pinfunction "1_1") (pintype "passive"))
      (node (ref "R41") (pin "1") (pinfunction "1_1") (pintype "passive"))
      (node (ref "R43") (pin "1") (pinfunction "1_1") (pintype "passive"))
      (node (ref "R48") (pin "1") (pinfunction "1_1") (pintype "passive"))
      (node (ref "R49") (pin "1") (pinfunction "1_1") (pintype "passive"))
      (node (ref "R50") (pin "1") (pinfunction "1_1") (pintype "passive"))
      (node (ref "RE1") (pin "8") (pinfunction "GND_8") (pintype "input"))
      (node (ref "U1") (pin "4") (pinfunction "GND_4") (pintype "power_in"))
      (node (ref "U10") (pin "4") (pinfunction "V-_4") (pintype "power_in"))
      (node (ref "U11") (pin "4") (pinfunction "GND_4") (pintype "power_in"))
      (node (ref "U11") (pin "9") (pinfunction "EP_9") (pintype "power_in"))
      (node (ref "U12") (pin "2") (pinfunction "GND_2") (pintype "power_in"))
      (node (ref "U19") (pin "4") (pinfunction "VCC-_4") (pintype "power_in"))
      (node (ref "U2") (pin "4") (pinfunction "GND_4") (pintype "power_in"))
      (node (ref "U22") (pin "4") (pinfunction "VCC-_4") (pintype "power_in"))
      (node (ref "U23") (pin "2") (pinfunction "K_2") (pintype "passive"))
      (node (ref "U26") (pin "4") (pinfunction "VCC-_4") (pintype "power_in"))
      (node (ref "U3") (pin "2") (pinfunction "GND_2") (pintype "power_in"))
      (node (ref "U30") (pin "4") (pinfunction "VCC-_4") (pintype "power_in"))
      (node (ref "U4") (pin "8") (pinfunction "VSS_8") (pintype "power_in"))
      (node (ref "U5") (pin "4") (pinfunction "V-_4") (pintype "power_in"))
      (node (ref "U6") (pin "4") (pinfunction "V-_4") (pintype "power_in"))
      (node (ref "U7") (pin "2") (pinfunction "VSS_2") (pintype "power_in"))
      (node (ref "U8") (pin "4") (pinfunction "V-_4") (pintype "power_in"))
      (node (ref "U8") (pin "5") (pinfunction "IN2+_5") (pintype "tri_state"))
      (node (ref "U8") (pin "6") (pinfunction "IN2-_6") (pintype "tri_state"))
      (node (ref "U8") (pin "7") (pinfunction "OUT2_7") (pintype "passive"))
      (node (ref "U9") (pin "CN10_20") (pinfunction "CN10_GND_CN10_20") (pintype "power_in"))
      (node (ref "U9") (pin "CN10_9") (pinfunction "CN10_GND_CN10_9") (pintype "power_in"))
      (node (ref "U9") (pin "CN7_19") (pinfunction "CN7_GND_CN7_19") (pintype "power_in"))
      (node (ref "U9") (pin "CN7_20") (pinfunction "CN7_GND_CN7_20") (pintype "power_in"))
      (node (ref "U9") (pin "CN7_22") (pinfunction "CN7_GND_CN7_22") (pintype "power_in"))
      (node (ref "U9") (pin "CN7_8") (pinfunction "CN7_GND_CN7_8") (pintype "power_in"))
    )
    (net (code "59") (name "Net-(APPS1-Pad2)") (class "Default")
      (node (ref "APPS1") (pin "2") (pintype "passive"))
      (node (ref "Pedals") (pin "2") (pintype "passive"))
    )
    (net (code "60") (name "Net-(APPS2-Pad2)") (class "Default")
      (node (ref "APPS2") (pin "2") (pintype "passive"))
      (node (ref "Pedals") (pin "5") (pintype "passive"))
    )
    (net (code "61") (name "Net-(BSE-Pad1)") (class "Default")
      (node (ref "BSE") (pin "1") (pintype "passive"))
      (node (ref "Pedals") (pin "8") (pintype "passive"))
    )
    (net (code "62") (name "Net-(D1-K)") (class "Default")
      (node (ref "C1") (pin "1") (pinfunction "1_1") (pintype "passive"))
      (node (ref "D1") (pin "2") (pinfunction "K_2") (pintype "passive"))
      (node (ref "K1") (pin "4") (pinfunction "4_4") (pintype "passive"))
      (node (ref "K1") (pin "8") (pinfunction "8_8") (pintype "passive"))
      (node (ref "K2") (pin "4") (pinfunction "4_4") (pintype "passive"))
    )
    (net (code "63") (name "Net-(D3-K)") (class "Default")
      (node (ref "C2") (pin "1") (pinfunction "1_1") (pintype "passive"))
      (node (ref "D3") (pin "2") (pinfunction "K_2") (pintype "passive"))
      (node (ref "K3") (pin "4") (pinfunction "4_4") (pintype "passive"))
      (node (ref "K3") (pin "8") (pinfunction "8_8") (pintype "passive"))
      (node (ref "K4") (pin "4") (pinfunction "4_4") (pintype "passive"))
    )
    (net (code "64") (name "Net-(D5-A)") (class "Default")
      (node (ref "D5") (pin "2") (pinfunction "A_2") (pintype "passive"))
      (node (ref "R45") (pin "1") (pinfunction "1_1") (pintype "passive"))
    )
    (net (code "65") (name "Net-(D7-A)") (class "Default")
      (node (ref "D7") (pin "2") (pinfunction "A_2") (pintype "passive"))
      (node (ref "R11") (pin "1") (pinfunction "1_1") (pintype "passive"))
    )
    (net (code "66") (name "Net-(D8-A)") (class "Default")
      (node (ref "D8") (pin "2") (pinfunction "A_2") (pintype "passive"))
      (node (ref "R14") (pin "1") (pinfunction "1_1") (pintype "passive"))
    )
    (net (code "67") (name "Net-(D9-A)") (class "Default")
      (node (ref "D9") (pin "2") (pinfunction "A_2") (pintype "passive"))
      (node (ref "R20") (pin "1") (pinfunction "1_1") (pintype "passive"))
    )
    (net (code "68") (name "Net-(D10-A)") (class "Default")
      (node (ref "D10") (pin "2") (pinfunction "A_2") (pintype "passive"))
      (node (ref "R35") (pin "1") (pinfunction "1_1") (pintype "passive"))
    )
    (net (code "69") (name "Net-(D11-A)") (class "Default")
      (node (ref "D11") (pin "2") (pinfunction "A_2") (pintype "passive"))
      (node (ref "R36") (pin "1") (pinfunction "1_1") (pintype "passive"))
    )
    (net (code "70") (name "Net-(D12-C)") (class "Default")
      (node (ref "D12") (pin "1") (pinfunction "C_1") (pintype "passive"))
      (node (ref "R38") (pin "2") (pinfunction "2_2") (pintype "passive"))
    )
    (net (code "71") (name "Net-(Q1-GATE)") (class "Default")
      (node (ref "Q1") (pin "1") (pinfunction "GATE_1") (pintype "passive"))
      (node (ref "Q2") (pin "1") (pinfunction "GATE_1") (pintype "passive"))
      (node (ref "R37") (pin "1") (pinfunction "1_1") (pintype "passive"))
      (node (ref "U30") (pin "1") (pinfunction "Out1_1") (pintype "passive"))
    )
    (net (code "72") (name "Net-(Q4-G)") (class "Default")
      (node (ref "Q4") (pin "1") (pinfunction "G_1") (pintype "passive"))
      (node (ref "U12") (pin "4") (pinfunction "Y_4") (pintype "output"))
    )
    (net (code "73") (name "Net-(Q5-G)") (class "Default")
      (node (ref "Q5") (pin "1") (pinfunction "G_1") (pintype "passive"))
      (node (ref "R3") (pin "1") (pinfunction "1_1") (pintype "passive"))
      (node (ref "U3") (pin "4") (pinfunction "Y_4") (pintype "output"))
    )
    (net (code "74") (name "Net-(U1A-1A)") (class "Default")
      (node (ref "R6") (pin "1") (pinfunction "1_1") (pintype "passive"))
      (node (ref "U1") (pin "1") (pinfunction "1A_1") (pintype "input"))
      (node (ref "U22") (pin "1") (pinfunction "Out1_1") (pintype "passive"))
    )
    (net (code "75") (name "Net-(U1A-1B)") (class "Default")
      (node (ref "R7") (pin "1") (pinfunction "1_1") (pintype "passive"))
      (node (ref "U1") (pin "2") (pinfunction "1B_2") (pintype "input"))
      (node (ref "U22") (pin "7") (pinfunction "Out2_7") (pintype "passive"))
    )
    (net (code "76") (name "Net-(U1B-2A)") (class "Default")
      (node (ref "R8") (pin "1") (pinfunction "1_1") (pintype "passive"))
      (node (ref "U1") (pin "5") (pinfunction "2A_5") (pintype "input"))
      (node (ref "U26") (pin "1") (pinfunction "Out1_1") (pintype "passive"))
    )
    (net (code "77") (name "Net-(U1B-2B)") (class "Default")
      (node (ref "R9") (pin "1") (pinfunction "1_1") (pintype "passive"))
      (node (ref "U1") (pin "6") (pinfunction "2B_6") (pintype "input"))
      (node (ref "U26") (pin "7") (pinfunction "Out2_7") (pintype "passive"))
    )
    (net (code "78") (name "Net-(U5A-IN1-)") (class "Default")
      (node (ref "R1") (pin "1") (pinfunction "1_1") (pintype "passive"))
      (node (ref "R4") (pin "2") (pinfunction "2_2") (pintype "passive"))
      (node (ref "U5") (pin "2") (pinfunction "IN1-_2") (pintype "tri_state"))
    )
    (net (code "79") (name "Net-(U5B-IN2-)") (class "Default")
      (node (ref "R10") (pin "1") (pinfunction "1_1") (pintype "passive"))
      (node (ref "R13") (pin "2") (pinfunction "2_2") (pintype "passive"))
      (node (ref "U5") (pin "6") (pinfunction "IN2-_6") (pintype "tri_state"))
    )
    (net (code "80") (name "Net-(U6A-IN1+)") (class "Default")
      (node (ref "R15") (pin "2") (pinfunction "2_2") (pintype "passive"))
      (node (ref "U6") (pin "1") (pinfunction "OUT1_1") (pintype "passive"))
      (node (ref "U6") (pin "3") (pinfunction "IN1+_3") (pintype "tri_state"))
    )
    (net (code "81") (name "Net-(U6A-IN1-)") (class "Default")
      (node (ref "C24") (pin "1") (pinfunction "1_1") (pintype "passive"))
      (node (ref "R34") (pin "2") (pinfunction "2_2") (pintype "passive"))
      (node (ref "U6") (pin "2") (pinfunction "IN1-_2") (pintype "tri_state"))
    )
    (net (code "82") (name "Net-(U6B-IN2+)") (class "Default")
      (node (ref "R19") (pin "2") (pinfunction "2_2") (pintype "passive"))
      (node (ref "U6") (pin "5") (pinfunction "IN2+_5") (pintype "tri_state"))
      (node (ref "U6") (pin "7") (pinfunction "OUT2_7") (pintype "passive"))
    )
    (net (code "83") (name "Net-(U6B-IN2-)") (class "Default")
      (node (ref "C29") (pin "1") (pinfunction "1_1") (pintype "passive"))
      (node (ref "R23") (pin "2") (pinfunction "2_2") (pintype "passive"))
      (node (ref "U6") (pin "6") (pinfunction "IN2-_6") (pintype "tri_state"))
    )
    (net (code "84") (name "Net-(U7-RS)") (class "Default")
      (node (ref "R21") (pin "2") (pinfunction "2_2") (pintype "passive"))
      (node (ref "U7") (pin "8") (pinfunction "RS_8") (pintype "input"))
    )
    (net (code "85") (name "Net-(U8A-IN1-)") (class "Default")
      (node (ref "C4") (pin "1") (pinfunction "1_1") (pintype "passive"))
      (node (ref "R5") (pin "2") (pinfunction "2_2") (pintype "passive"))
      (node (ref "U8") (pin "2") (pinfunction "IN1-_2") (pintype "tri_state"))
    )
    (net (code "86") (name "Net-(U10A-IN1+)") (class "Default")
      (node (ref "R28") (pin "2") (pinfunction "2_2") (pintype "passive"))
      (node (ref "U10") (pin "1") (pinfunction "OUT1_1") (pintype "passive"))
      (node (ref "U10") (pin "3") (pinfunction "IN1+_3") (pintype "tri_state"))
    )
    (net (code "87") (name "Net-(U10A-IN1-)") (class "Default")
      (node (ref "C7") (pin "1") (pinfunction "1_1") (pintype "passive"))
      (node (ref "R40") (pin "2") (pinfunction "2_2") (pintype "passive"))
      (node (ref "U10") (pin "2") (pinfunction "IN1-_2") (pintype "tri_state"))
    )
    (net (code "88") (name "Net-(U11-SS)") (class "Default")
      (node (ref "C11") (pin "1") (pinfunction "1_1") (pintype "passive"))
      (node (ref "U11") (pin "6") (pinfunction "SS_6") (pintype "output"))
    )
    (net (code "89") (name "Net-(U12A-A)") (class "Default")
      (node (ref "R44") (pin "1") (pinfunction "1_1") (pintype "passive"))
      (node (ref "R48") (pin "2") (pinfunction "2_2") (pintype "passive"))
      (node (ref "U12") (pin "1") (pinfunction "A_1") (pintype "input"))
    )
    (net (code "90") (name "Net-(U12A-B)") (class "Default")
      (node (ref "R46") (pin "1") (pinfunction "1_1") (pintype "passive"))
      (node (ref "R49") (pin "2") (pinfunction "2_2") (pintype "passive"))
      (node (ref "U12") (pin "3") (pinfunction "B_3") (pintype "input"))
    )
    (net (code "91") (name "Net-(U12A-C)") (class "Default")
      (node (ref "R47") (pin "1") (pinfunction "1_1") (pintype "passive"))
      (node (ref "R50") (pin "2") (pinfunction "2_2") (pintype "passive"))
      (node (ref "U12") (pin "6") (pinfunction "C_6") (pintype "input"))
    )
    (net (code "92") (name "Net-(U16-A)") (class "Default")
      (node (ref "R2") (pin "2") (pinfunction "2_2") (pintype "passive"))
      (node (ref "U16") (pin "1") (pinfunction "A_1") (pintype "passive"))
    )
    (net (code "93") (name "Net-(U19A-In1+)") (class "Default")
      (node (ref "Current Sensor Inverted Select") (pin "2") (pinfunction "2_2") (pintype "passive"))
      (node (ref "U19") (pin "3") (pinfunction "In1+_3") (pintype "tri_state"))
    )
    (net (code "94") (name "Net-(U19A-In1-)") (class "Default")
      (node (ref "Current Sensor Inverted Select2") (pin "2") (pinfunction "2_2") (pintype "passive"))
      (node (ref "U19") (pin "2") (pinfunction "In1-_2") (pintype "tri_state"))
    )
    (net (code "95") (name "Net-(U19A-Out1)") (class "Default")
      (node (ref "R16") (pin "1") (pinfunction "1_1") (pintype "passive"))
      (node (ref "U19") (pin "1") (pinfunction "Out1_1") (pintype "passive"))
      (node (ref "U2") (pin "1") (pinfunction "1A_1") (pintype "input"))
    )
    (net (code "96") (name "Net-(U19B-In2+)") (class "Default")
      (node (ref "C30") (pin "2") (pinfunction "2_2") (pintype "passive"))
      (node (ref "R25") (pin "2") (pinfunction "2_2") (pintype "passive"))
      (node (ref "U19") (pin "5") (pinfunction "In2+_5") (pintype "tri_state"))
    )
    (net (code "97") (name "Net-(U19B-Out2)") (class "Default")
      (node (ref "R24") (pin "1") (pinfunction "1_1") (pintype "passive"))
      (node (ref "U19") (pin "7") (pinfunction "Out2_7") (pintype "passive"))
      (node (ref "U2") (pin "6") (pinfunction "2B_6") (pintype "input"))
    )
    (net (code "98") (name "Net-(U23-A)") (class "Default")
      (node (ref "R3") (pin "2") (pinfunction "2_2") (pintype "passive"))
      (node (ref "U23") (pin "1") (pinfunction "A_1") (pintype "passive"))
    )
    (net (code "99") (name "Net-(U23-E)") (class "Default")
      (node (ref "K3") (pin "7") (pinfunction "7_7") (pintype "passive"))
      (node (ref "K4") (pin "2") (pinfunction "2_2") (pintype "passive"))
      (node (ref "U23") (pin "3") (pinfunction "E_3") (pintype "passive"))
    )
    (net (code "100") (name "Net-(U30A-In1+)") (class "Default")
      (node (ref "Brake Invert") (pin "2") (pinfunction "2_2") (pintype "passive"))
      (node (ref "U30") (pin "3") (pinfunction "In1+_3") (pintype "tri_state"))
    )
    (net (code "101") (name "Net-(U30A-In1-)") (class "Default")
      (node (ref "Brake invert2") (pin "2") (pinfunction "2_2") (pintype "passive"))
      (node (ref "U30") (pin "2") (pinfunction "In1-_2") (pintype "tri_state"))
    )
    (net (code "102") (name "Net-(U30B-In2+)") (class "Default")
      (node (ref "HBrake Invert1") (pin "2") (pinfunction "2_2") (pintype "passive"))
      (node (ref "U30") (pin "5") (pinfunction "In2+_5") (pintype "tri_state"))
    )
    (net (code "103") (name "Net-(U30B-In2-)") (class "Default")
      (node (ref "Hvy Brk Inv") (pin "2") (pinfunction "2_2") (pintype "passive"))
      (node (ref "U30") (pin "6") (pinfunction "In2-_6") (pintype "tri_state"))
    )
    (net (code "104") (name "unconnected-(Pedals-Pad11)") (class "Default")
      (node (ref "Pedals") (pin "11") (pintype "passive"))
    )
    (net (code "105") (name "unconnected-(Pedals-Pad12)") (class "Default")
      (node (ref "Pedals") (pin "12") (pintype "passive"))
    )
    (net (code "106") (name "unconnected-(RE1-D0{slash}S0-Pad6)") (class "Default")
      (node (ref "RE1") (pin "6") (pinfunction "D0/S0_6") (pintype "input"))
    )
    (net (code "107") (name "unconnected-(RE1-D3{slash}CS-Pad4)") (class "Default")
      (node (ref "RE1") (pin "4") (pinfunction "D3/CS_4") (pintype "input"))
    )
    (net (code "108") (name "unconnected-(U4-C-Pad10)") (class "Default")
      (node (ref "U4") (pin "10") (pinfunction "C_10") (pintype "input"))
    )
    (net (code "109") (name "unconnected-(U4-D-Pad14)") (class "Default")
      (node (ref "U4") (pin "14") (pinfunction "D_14") (pintype "input"))
    )
    (net (code "110") (name "unconnected-(U4-G-Pad11)") (class "Default")
      (node (ref "U4") (pin "11") (pinfunction "G_11") (pintype "output"))
    )
    (net (code "111") (name "unconnected-(U4-H-Pad13)") (class "Default")
      (node (ref "U4") (pin "13") (pinfunction "H_13") (pintype "output"))
    )
    (net (code "112") (name "unconnected-(U4-NC-Pad12)") (class "Default")
      (node (ref "U4") (pin "12") (pinfunction "NC_12") (pintype "passive"))
    )
    (net (code "113") (name "unconnected-(U7-VREF-Pad5)") (class "Default")
      (node (ref "U7") (pin "5") (pinfunction "VREF_5") (pintype "power_in"))
    )
    (net (code "114") (name "unconnected-(U9A-BOOT0-PadCN7_7)") (class "Default")
      (node (ref "U9") (pin "CN7_7") (pinfunction "BOOT0_CN7_7") (pintype "bidirectional"))
    )
    (net (code "115") (name "unconnected-(U9A-CN7_IOREF-PadCN7_12)") (class "Default")
      (node (ref "U9") (pin "CN7_12") (pinfunction "CN7_IOREF_CN7_12") (pintype "bidirectional"))
    )
    (net (code "116") (name "unconnected-(U9A-CN7_RESET-PadCN7_14)") (class "Default")
      (node (ref "U9") (pin "CN7_14") (pinfunction "CN7_RESET_CN7_14") (pintype "bidirectional"))
    )
    (net (code "117") (name "unconnected-(U9A-CN7_VIN-PadCN7_24)") (class "Default")
      (node (ref "U9") (pin "CN7_24") (pinfunction "CN7_VIN_CN7_24") (pintype "power_in"))
    )
    (net (code "118") (name "unconnected-(U9A-E5V-PadCN7_6)") (class "Default")
      (node (ref "U9") (pin "CN7_6") (pinfunction "E5V_CN7_6") (pintype "power_in"))
    )
    (net (code "119") (name "unconnected-(U9A-PA13-PadCN7_13)") (class "Default")
      (node (ref "U9") (pin "CN7_13") (pinfunction "PA13_CN7_13") (pintype "bidirectional"))
    )
    (net (code "120") (name "unconnected-(U9A-PA14-PadCN7_15)") (class "Default")
      (node (ref "U9") (pin "CN7_15") (pinfunction "PA14_CN7_15") (pintype "bidirectional"))
    )
    (net (code "121") (name "unconnected-(U9A-PA15-PadCN7_17)") (class "Default")
      (node (ref "U9") (pin "CN7_17") (pinfunction "PA15_CN7_17") (pintype "bidirectional"))
    )
    (net (code "122") (name "unconnected-(U9A-PB0-PadCN7_34)") (class "Default")
      (node (ref "U9") (pin "CN7_34") (pinfunction "PB0_CN7_34") (pintype "bidirectional"))
    )
    (net (code "123") (name "unconnected-(U9A-PB7-PadCN7_21)") (class "Default")
      (node (ref "U9") (pin "CN7_21") (pinfunction "PB7_CN7_21") (pintype "bidirectional"))
    )
    (net (code "124") (name "unconnected-(U9A-PC3-PadCN7_37)") (class "Default")
      (node (ref "U9") (pin "CN7_37") (pinfunction "PC3_CN7_37") (pintype "bidirectional"))
    )
    (net (code "125") (name "unconnected-(U9A-PC10-PadCN7_1)") (class "Default")
      (node (ref "U9") (pin "CN7_1") (pinfunction "PC10_CN7_1") (pintype "bidirectional"))
    )
    (net (code "126") (name "unconnected-(U9A-PC11-PadCN7_2)") (class "Default")
      (node (ref "U9") (pin "CN7_2") (pinfunction "PC11_CN7_2") (pintype "bidirectional"))
    )
    (net (code "127") (name "unconnected-(U9A-PC12-PadCN7_3)") (class "Default")
      (node (ref "U9") (pin "CN7_3") (pinfunction "PC12_CN7_3") (pintype "bidirectional"))
    )
    (net (code "128") (name "unconnected-(U9A-PC13-PadCN7_23)") (class "Default")
      (node (ref "U9") (pin "CN7_23") (pinfunction "PC13_CN7_23") (pintype "bidirectional"))
    )
    (net (code "129") (name "unconnected-(U9A-PC14-PadCN7_25)") (class "Default")
      (node (ref "U9") (pin "CN7_25") (pinfunction "PC14_CN7_25") (pintype "bidirectional"))
    )
    (net (code "130") (name "unconnected-(U9A-PC15-PadCN7_27)") (class "Default")
      (node (ref "U9") (pin "CN7_27") (pinfunction "PC15_CN7_27") (pintype "bidirectional"))
    )
    (net (code "131") (name "unconnected-(U9A-PD2-PadCN7_4)") (class "Default")
      (node (ref "U9") (pin "CN7_4") (pinfunction "PD2_CN7_4") (pintype "bidirectional"))
    )
    (net (code "132") (name "unconnected-(U9A-PH0-PadCN7_29)") (class "Default")
      (node (ref "U9") (pin "CN7_29") (pinfunction "PH0_CN7_29") (pintype "bidirectional"))
    )
    (net (code "133") (name "unconnected-(U9A-PH1-PadCN7_31)") (class "Default")
      (node (ref "U9") (pin "CN7_31") (pinfunction "PH1_CN7_31") (pintype "bidirectional"))
    )
    (net (code "134") (name "unconnected-(U9A-VBAT-PadCN7_33)") (class "Default")
      (node (ref "U9") (pin "CN7_33") (pinfunction "VBAT_CN7_33") (pintype "power_in"))
    )
    (net (code "135") (name "unconnected-(U9A-VDD-PadCN7_5)") (class "Default")
      (node (ref "U9") (pin "CN7_5") (pinfunction "VDD_CN7_5") (pintype "power_in"))
    )
    (net (code "136") (name "unconnected-(U9B-AGND-PadCN10_32)") (class "Default")
      (node (ref "U9") (pin "CN10_32") (pinfunction "AGND_CN10_32") (pintype "power_in"))
    )
    (net (code "137") (name "unconnected-(U9B-AVDD-PadCN10_7)") (class "Default")
      (node (ref "U9") (pin "CN10_7") (pinfunction "AVDD_CN10_7") (pintype "power_in"))
    )
    (net (code "138") (name "unconnected-(U9B-PA2-PadCN10_35)") (class "Default")
      (node (ref "U9") (pin "CN10_35") (pinfunction "PA2_CN10_35") (pintype "bidirectional"))
    )
    (net (code "139") (name "unconnected-(U9B-PA3-PadCN10_37)") (class "Default")
      (node (ref "U9") (pin "CN10_37") (pinfunction "PA3_CN10_37") (pintype "bidirectional"))
    )
    (net (code "140") (name "unconnected-(U9B-PA8-PadCN10_23)") (class "Default")
      (node (ref "U9") (pin "CN10_23") (pinfunction "PA8_CN10_23") (pintype "bidirectional"))
    )
    (net (code "141") (name "unconnected-(U9B-PA9-PadCN10_21)") (class "Default")
      (node (ref "U9") (pin "CN10_21") (pinfunction "PA9_CN10_21") (pintype "bidirectional"))
    )
    (net (code "142") (name "unconnected-(U9B-PA10-PadCN10_33)") (class "Default")
      (node (ref "U9") (pin "CN10_33") (pinfunction "PA10_CN10_33") (pintype "bidirectional"))
    )
    (net (code "143") (name "unconnected-(U9B-PB1-PadCN10_24)") (class "Default")
      (node (ref "U9") (pin "CN10_24") (pinfunction "PB1_CN10_24") (pintype "bidirectional"))
    )
    (net (code "144") (name "unconnected-(U9B-PB2-PadCN10_22)") (class "Default")
      (node (ref "U9") (pin "CN10_22") (pinfunction "PB2_CN10_22") (pintype "bidirectional"))
    )
    (net (code "145") (name "unconnected-(U9B-PB4-PadCN10_27)") (class "Default")
      (node (ref "U9") (pin "CN10_27") (pinfunction "PB4_CN10_27") (pintype "bidirectional"))
    )
    (net (code "146") (name "unconnected-(U9B-PB5-PadCN10_29)") (class "Default")
      (node (ref "U9") (pin "CN10_29") (pinfunction "PB5_CN10_29") (pintype "bidirectional"))
    )
    (net (code "147") (name "unconnected-(U9B-PB8-PadCN10_3)") (class "Default")
      (node (ref "U9") (pin "CN10_3") (pinfunction "PB8_CN10_3") (pintype "bidirectional"))
    )
    (net (code "148") (name "unconnected-(U9B-PB9-PadCN10_5)") (class "Default")
      (node (ref "U9") (pin "CN10_5") (pinfunction "PB9_CN10_5") (pintype "bidirectional"))
    )
    (net (code "149") (name "unconnected-(U9B-PB10-PadCN10_25)") (class "Default")
      (node (ref "U9") (pin "CN10_25") (pinfunction "PB10_CN10_25") (pintype "bidirectional"))
    )
    (net (code "150") (name "unconnected-(U9B-PB12-PadCN10_16)") (class "Default")
      (node (ref "U9") (pin "CN10_16") (pinfunction "PB12_CN10_16") (pintype "bidirectional"))
    )
    (net (code "151") (name "unconnected-(U9B-PB13-PadCN10_30)") (class "Default")
      (node (ref "U9") (pin "CN10_30") (pinfunction "PB13_CN10_30") (pintype "bidirectional"))
    )
    (net (code "152") (name "unconnected-(U9B-PB14-PadCN10_28)") (class "Default")
      (node (ref "U9") (pin "CN10_28") (pinfunction "PB14_CN10_28") (pintype "bidirectional"))
    )
    (net (code "153") (name "unconnected-(U9B-PB15-PadCN10_26)") (class "Default")
      (node (ref "U9") (pin "CN10_26") (pinfunction "PB15_CN10_26") (pintype "bidirectional"))
    )
    (net (code "154") (name "unconnected-(U9B-PC4-PadCN10_34)") (class "Default")
      (node (ref "U9") (pin "CN10_34") (pinfunction "PC4_CN10_34") (pintype "bidirectional"))
    )
    (net (code "155") (name "unconnected-(U9B-PC5-PadCN10_6)") (class "Default")
      (node (ref "U9") (pin "CN10_6") (pinfunction "PC5_CN10_6") (pintype "bidirectional"))
    )
    (net (code "156") (name "unconnected-(U9B-PC6-PadCN10_4)") (class "Default")
      (node (ref "U9") (pin "CN10_4") (pinfunction "PC6_CN10_4") (pintype "bidirectional"))
    )
    (net (code "157") (name "unconnected-(U9B-U5V-PadCN10_8)") (class "Default")
      (node (ref "U9") (pin "CN10_8") (pinfunction "U5V_CN10_8") (pintype "power_in"))
    )
  )
)
